# backplane.net
KiCad netlist of a schematic drawn in EAGLE
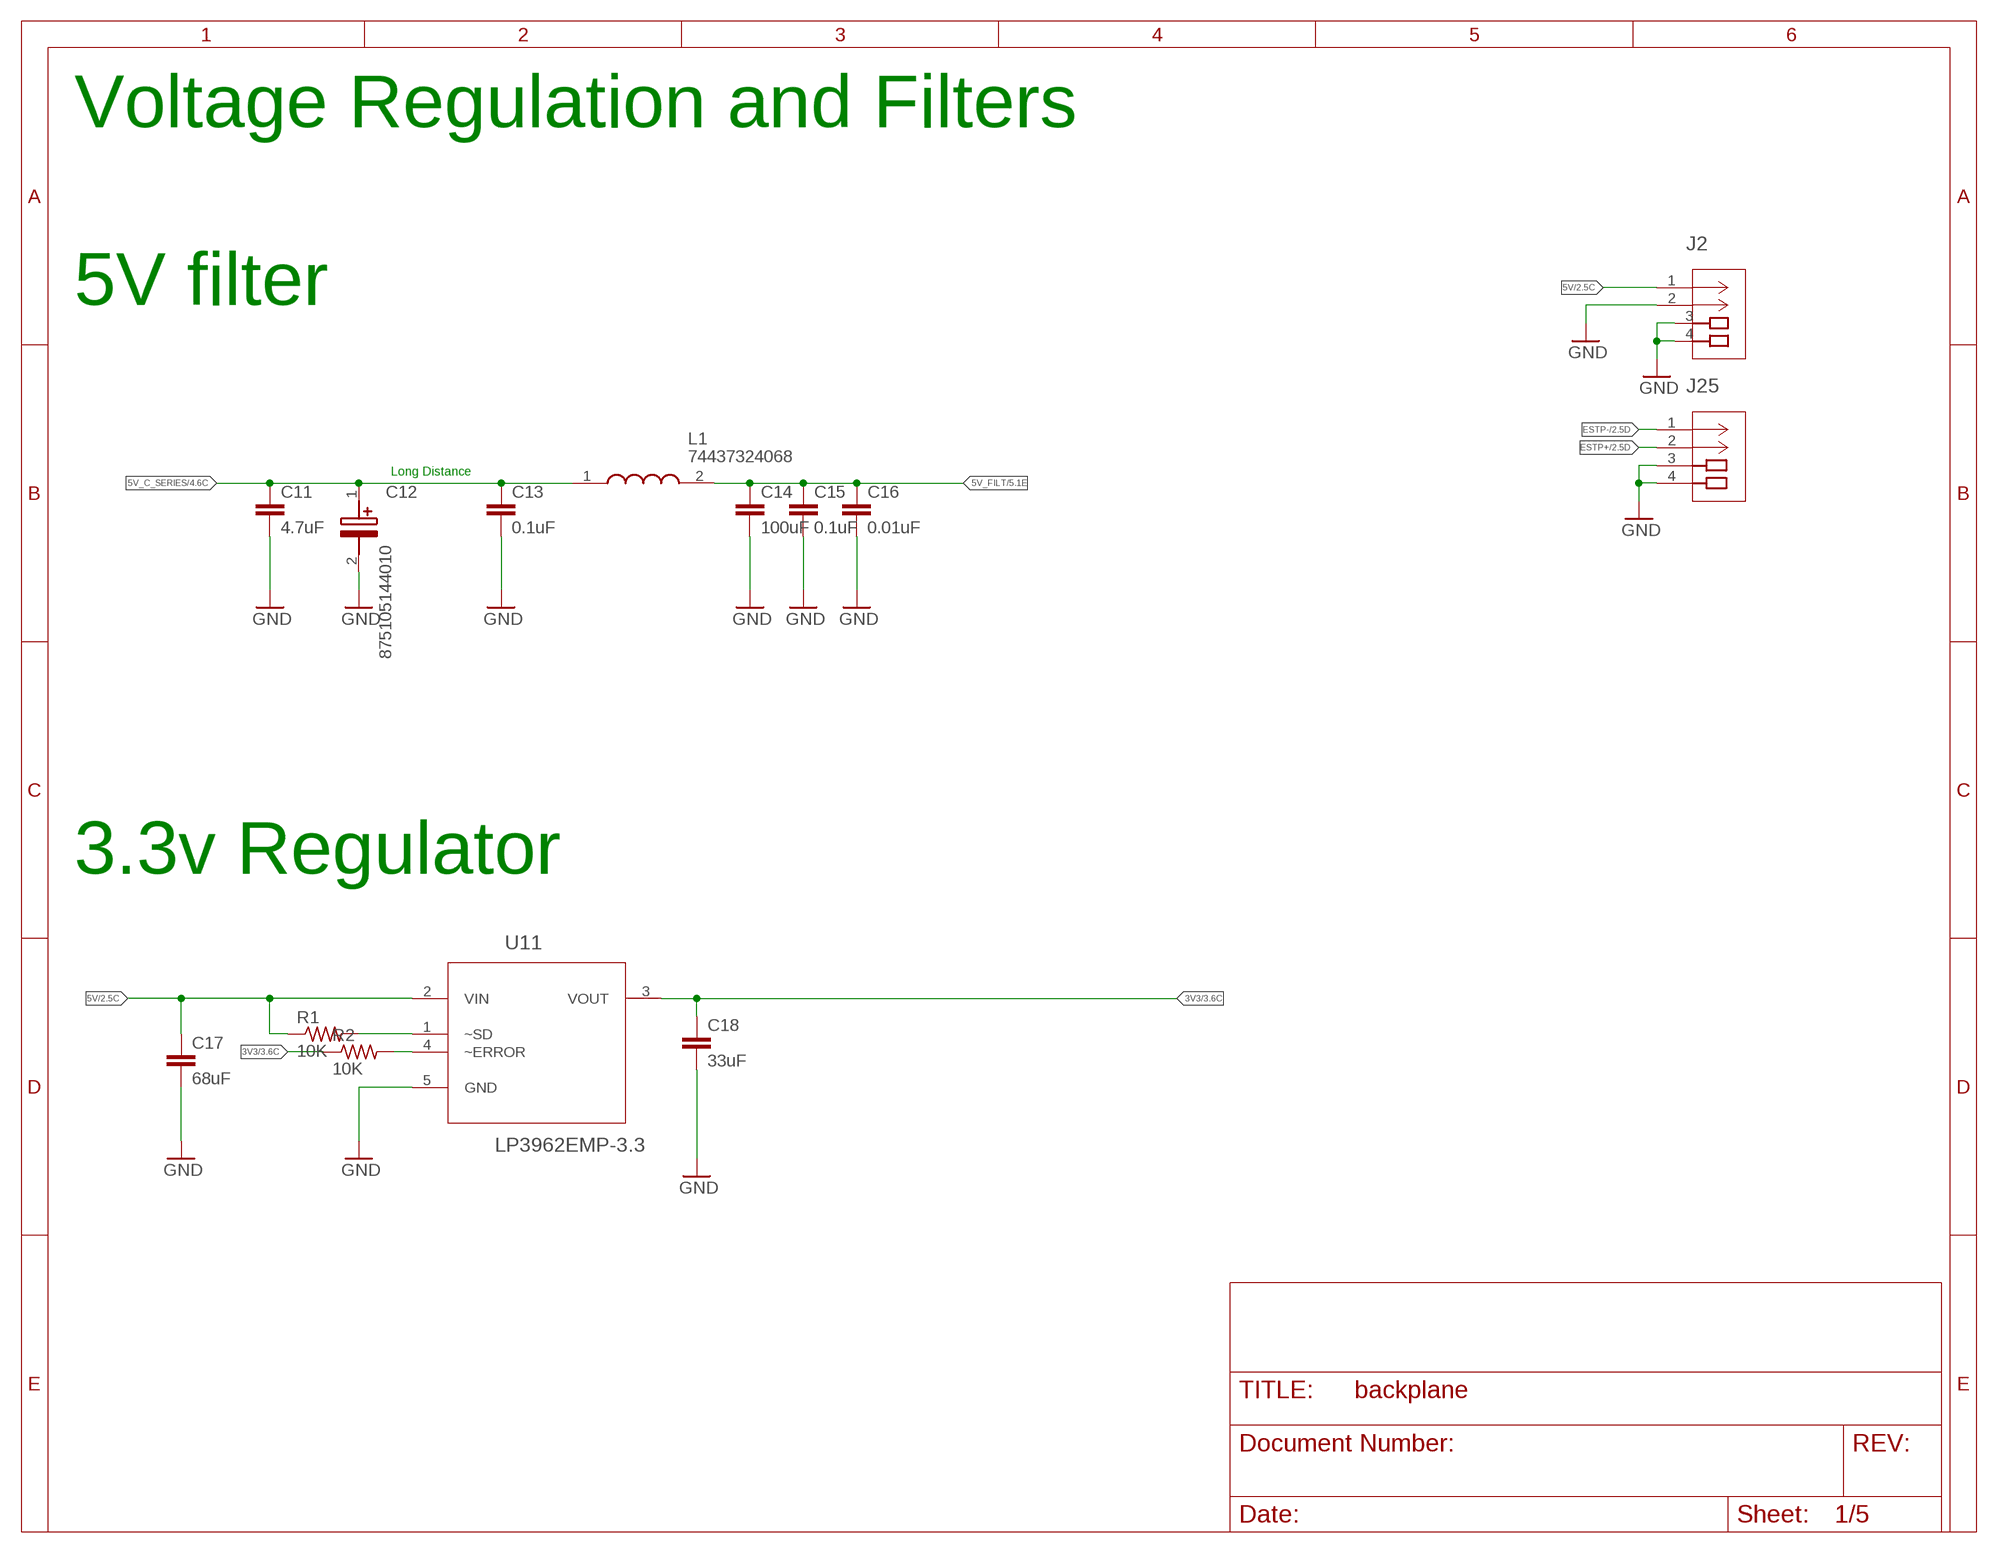
[diagram p0: schematic, sheet 1]
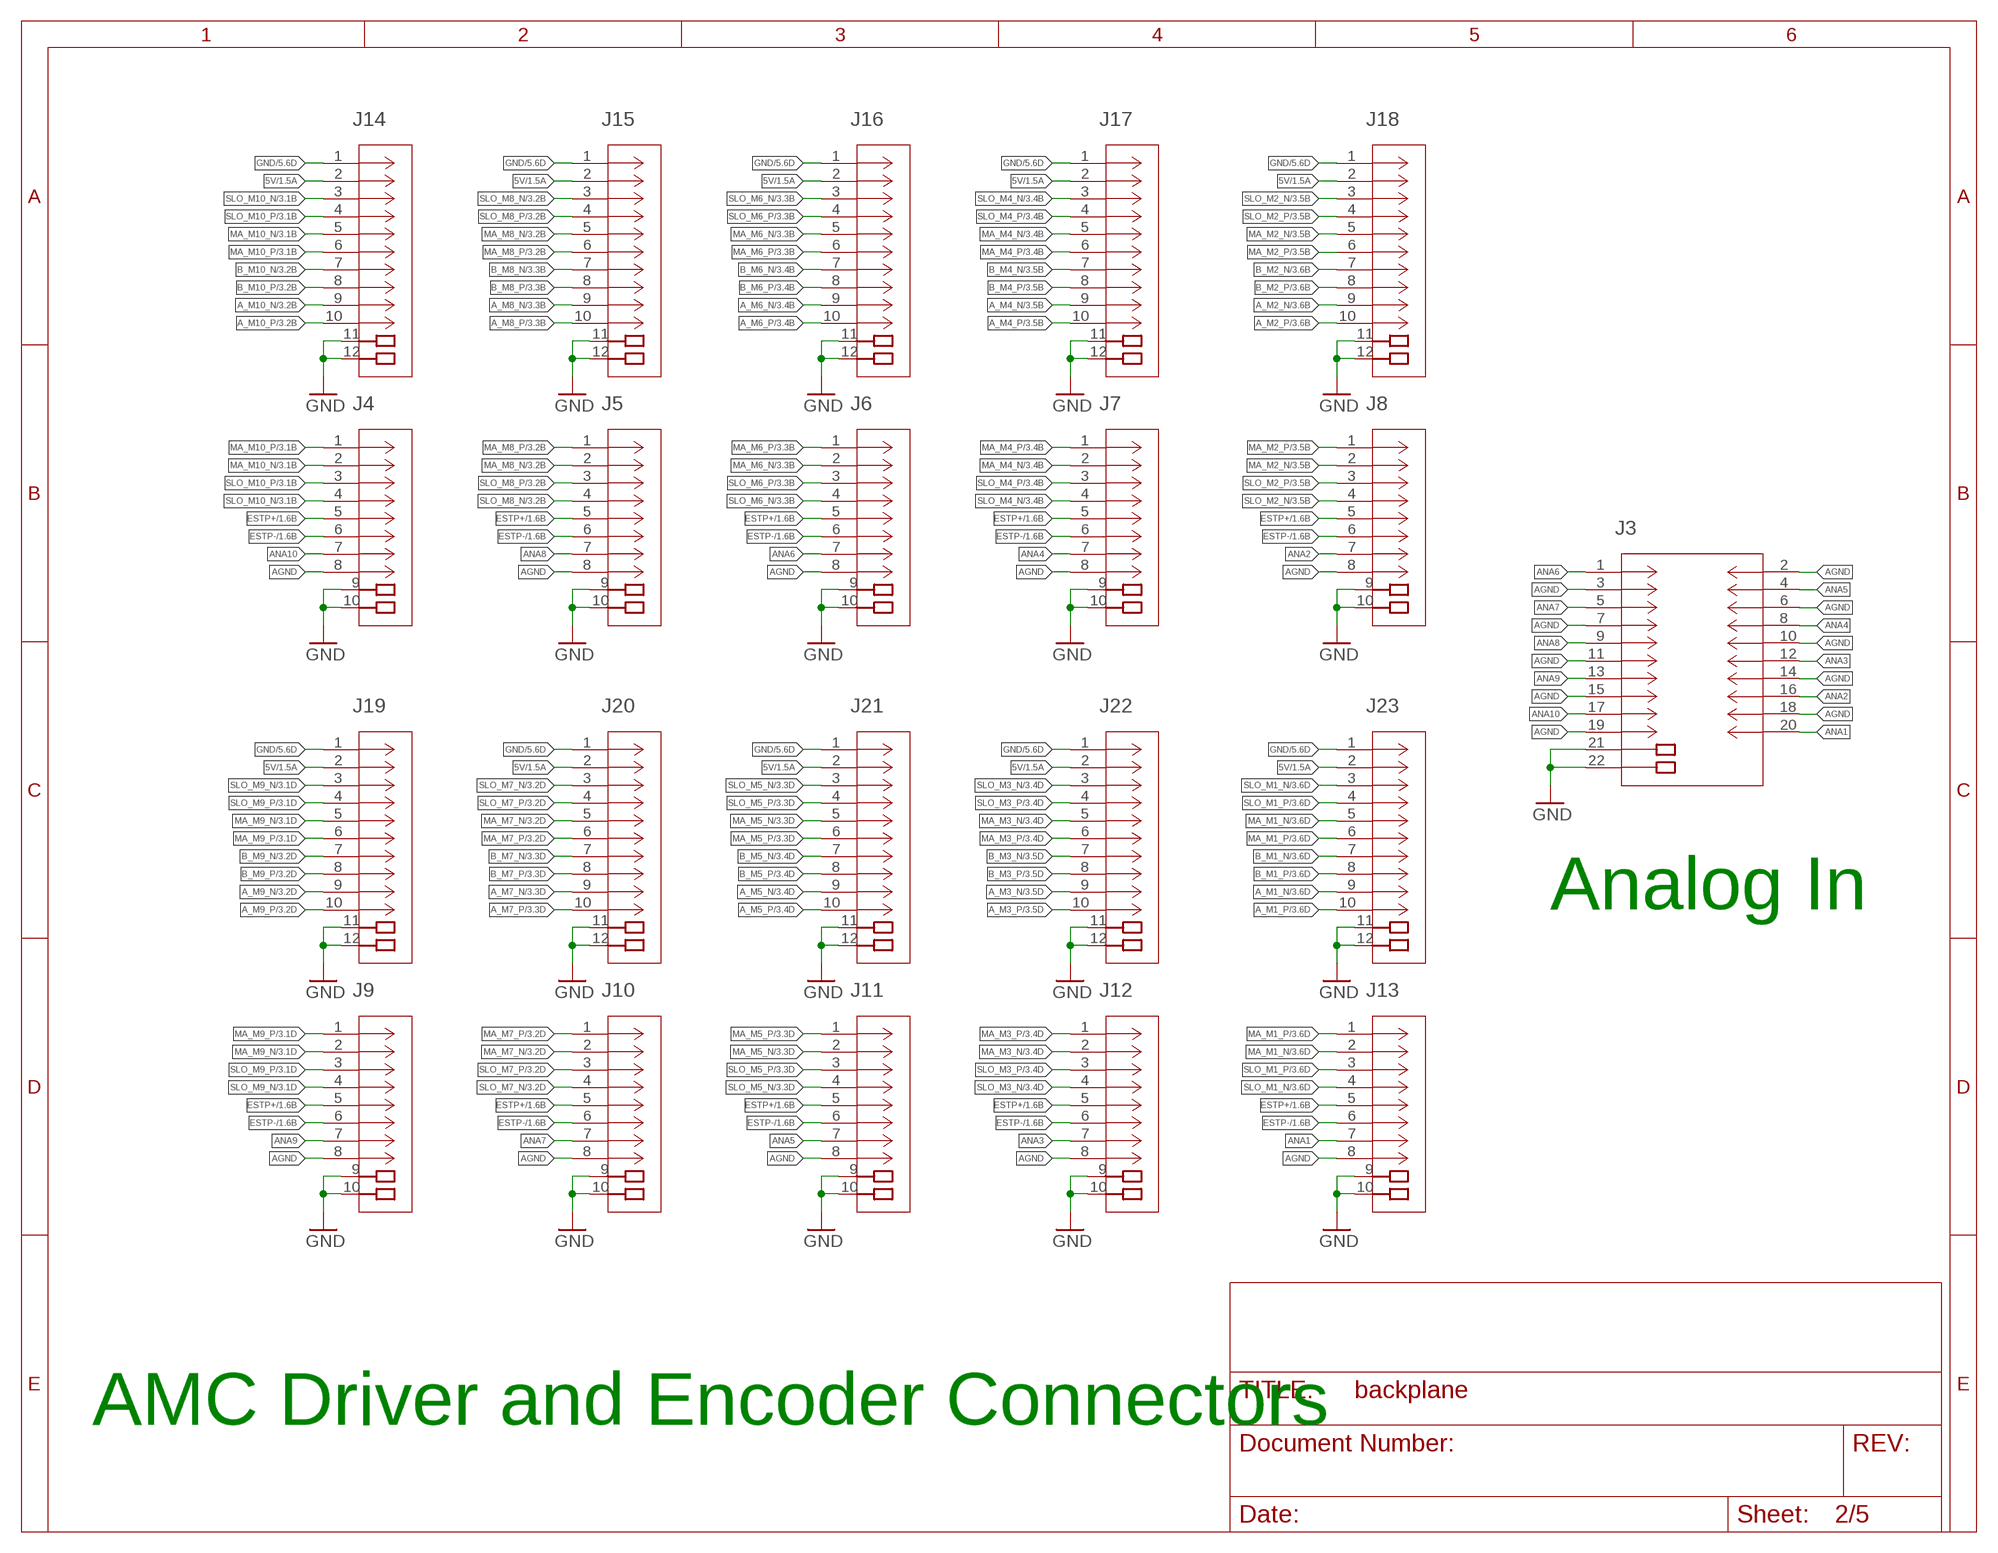
[diagram p1: schematic, sheet 2]
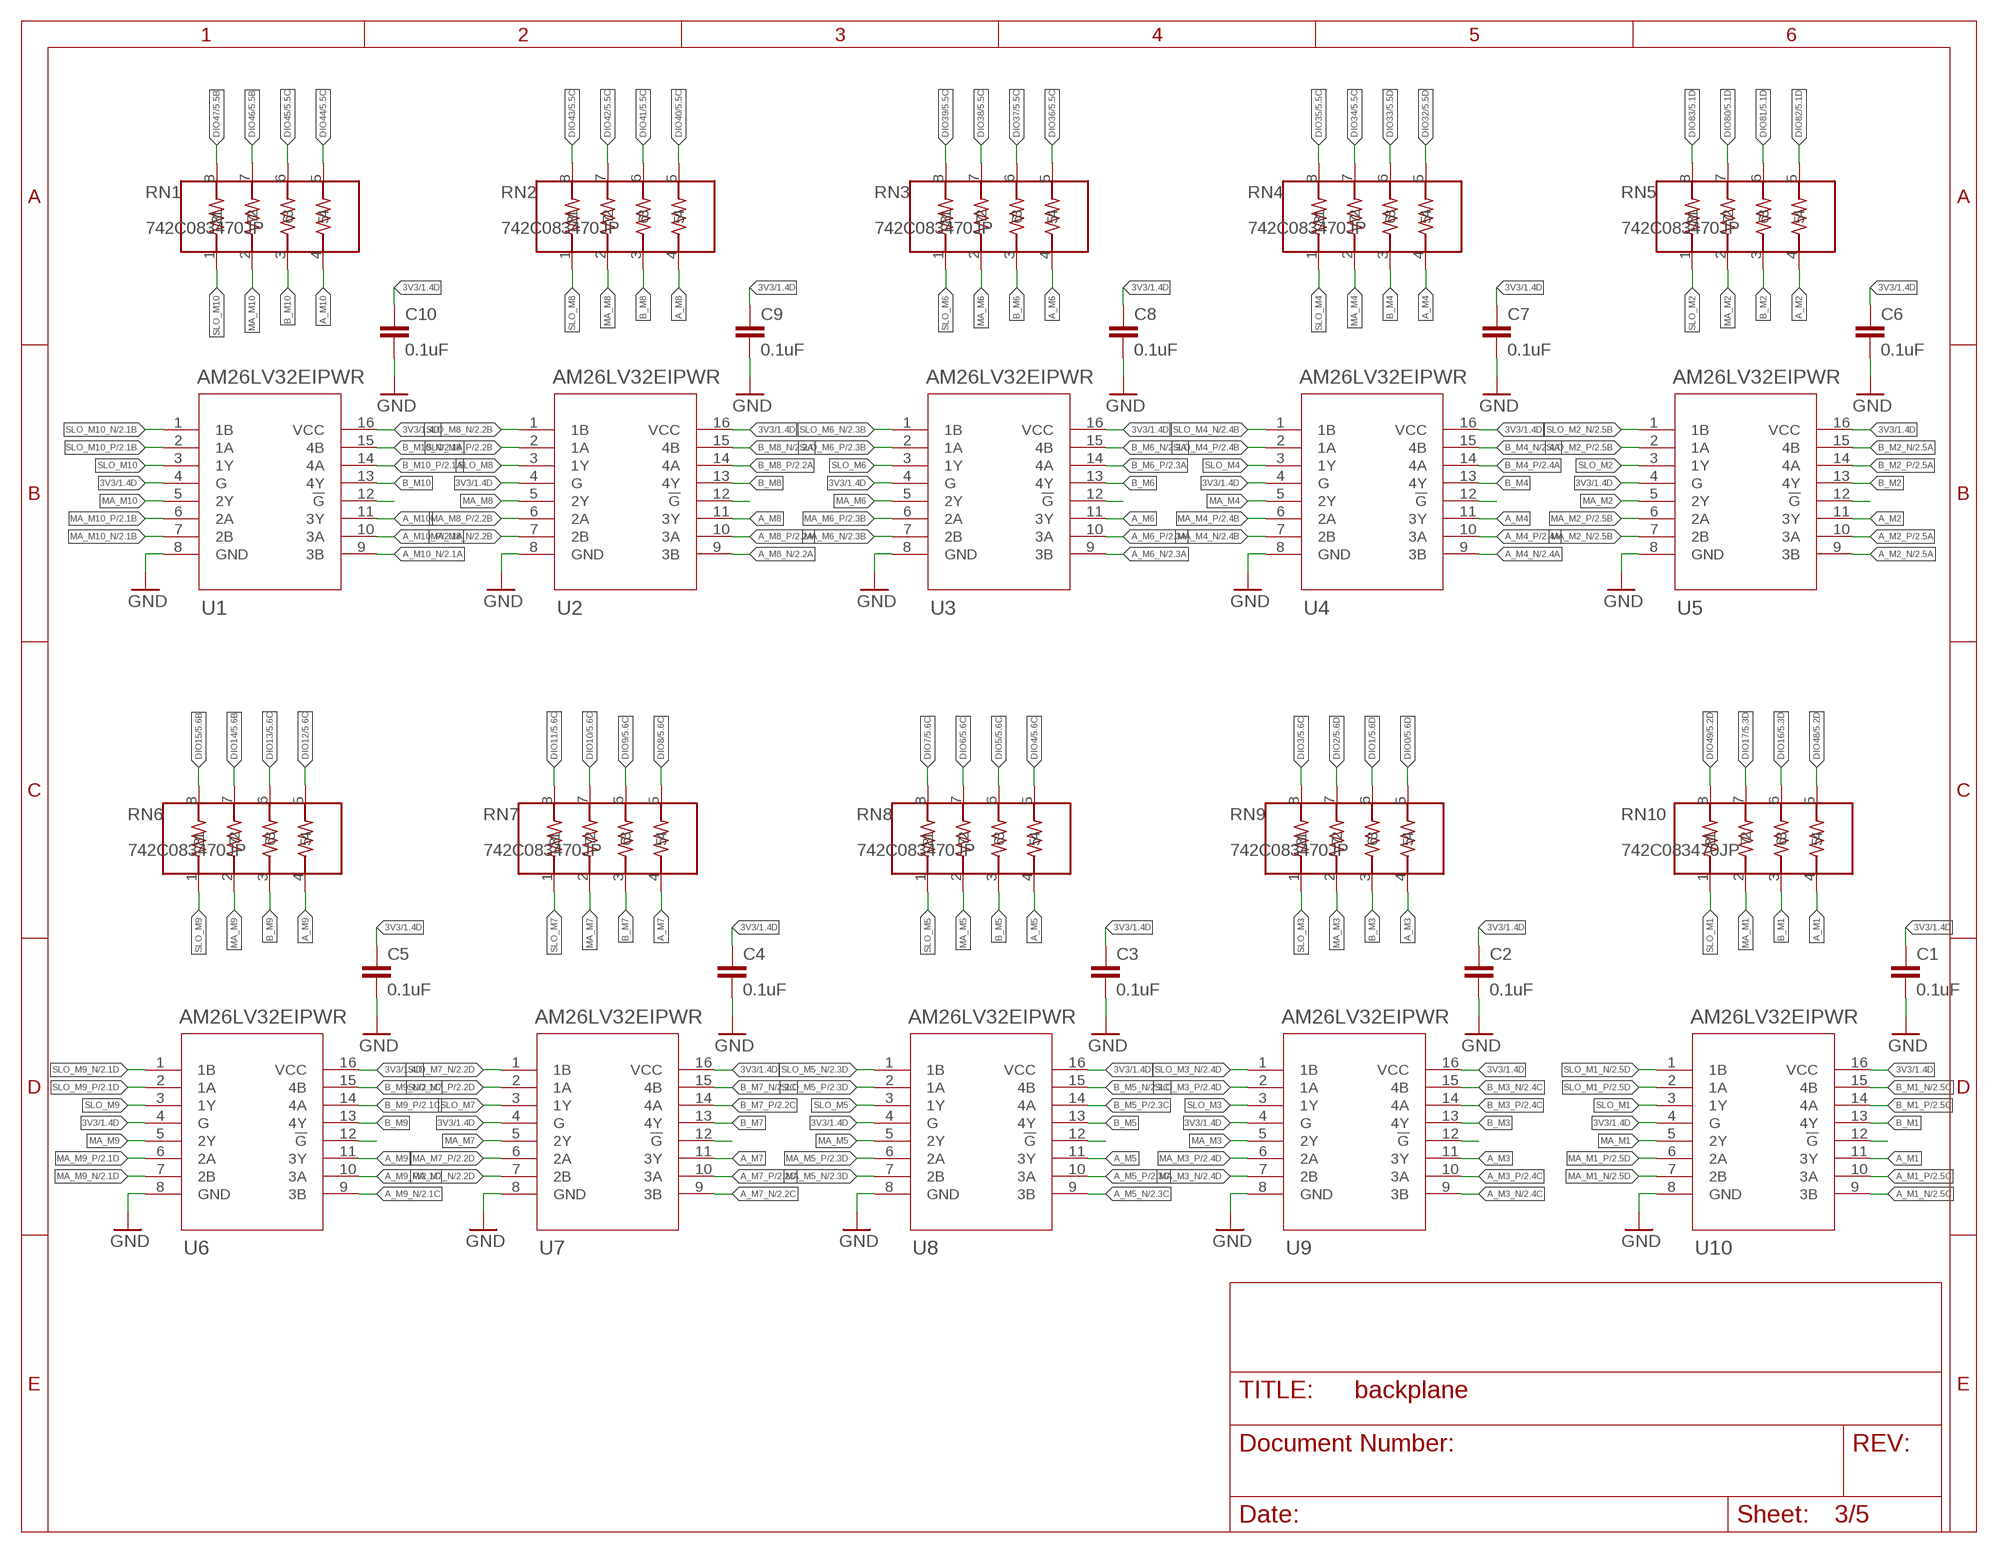
[diagram p2: schematic, sheet 3]
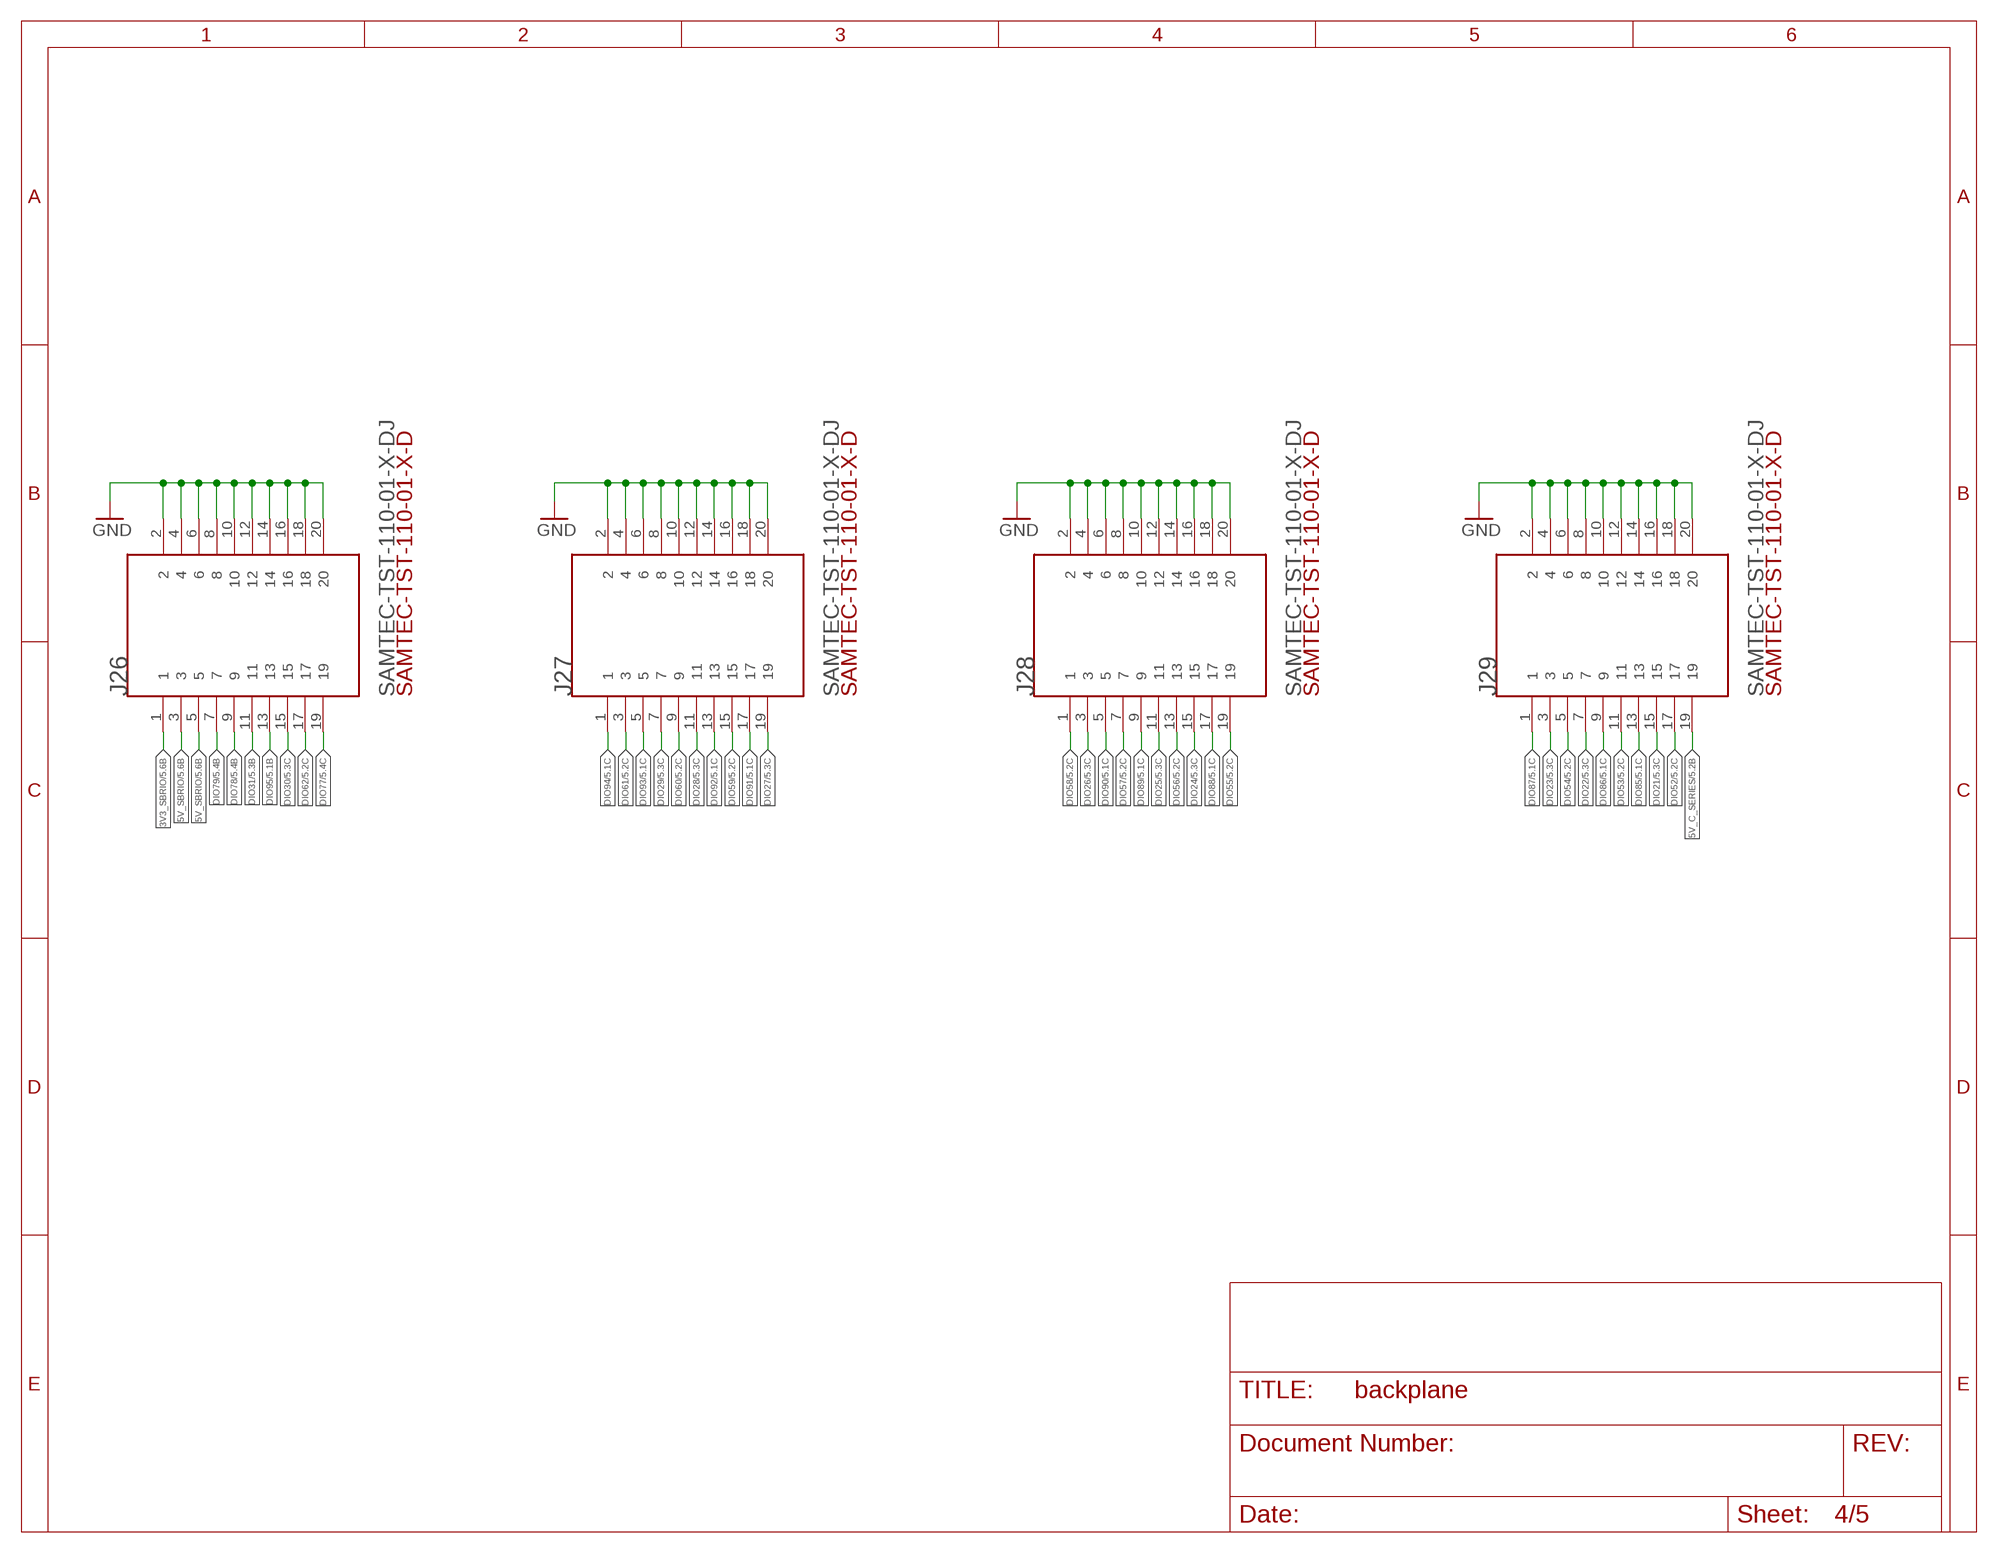
[diagram p3: schematic, sheet 4]
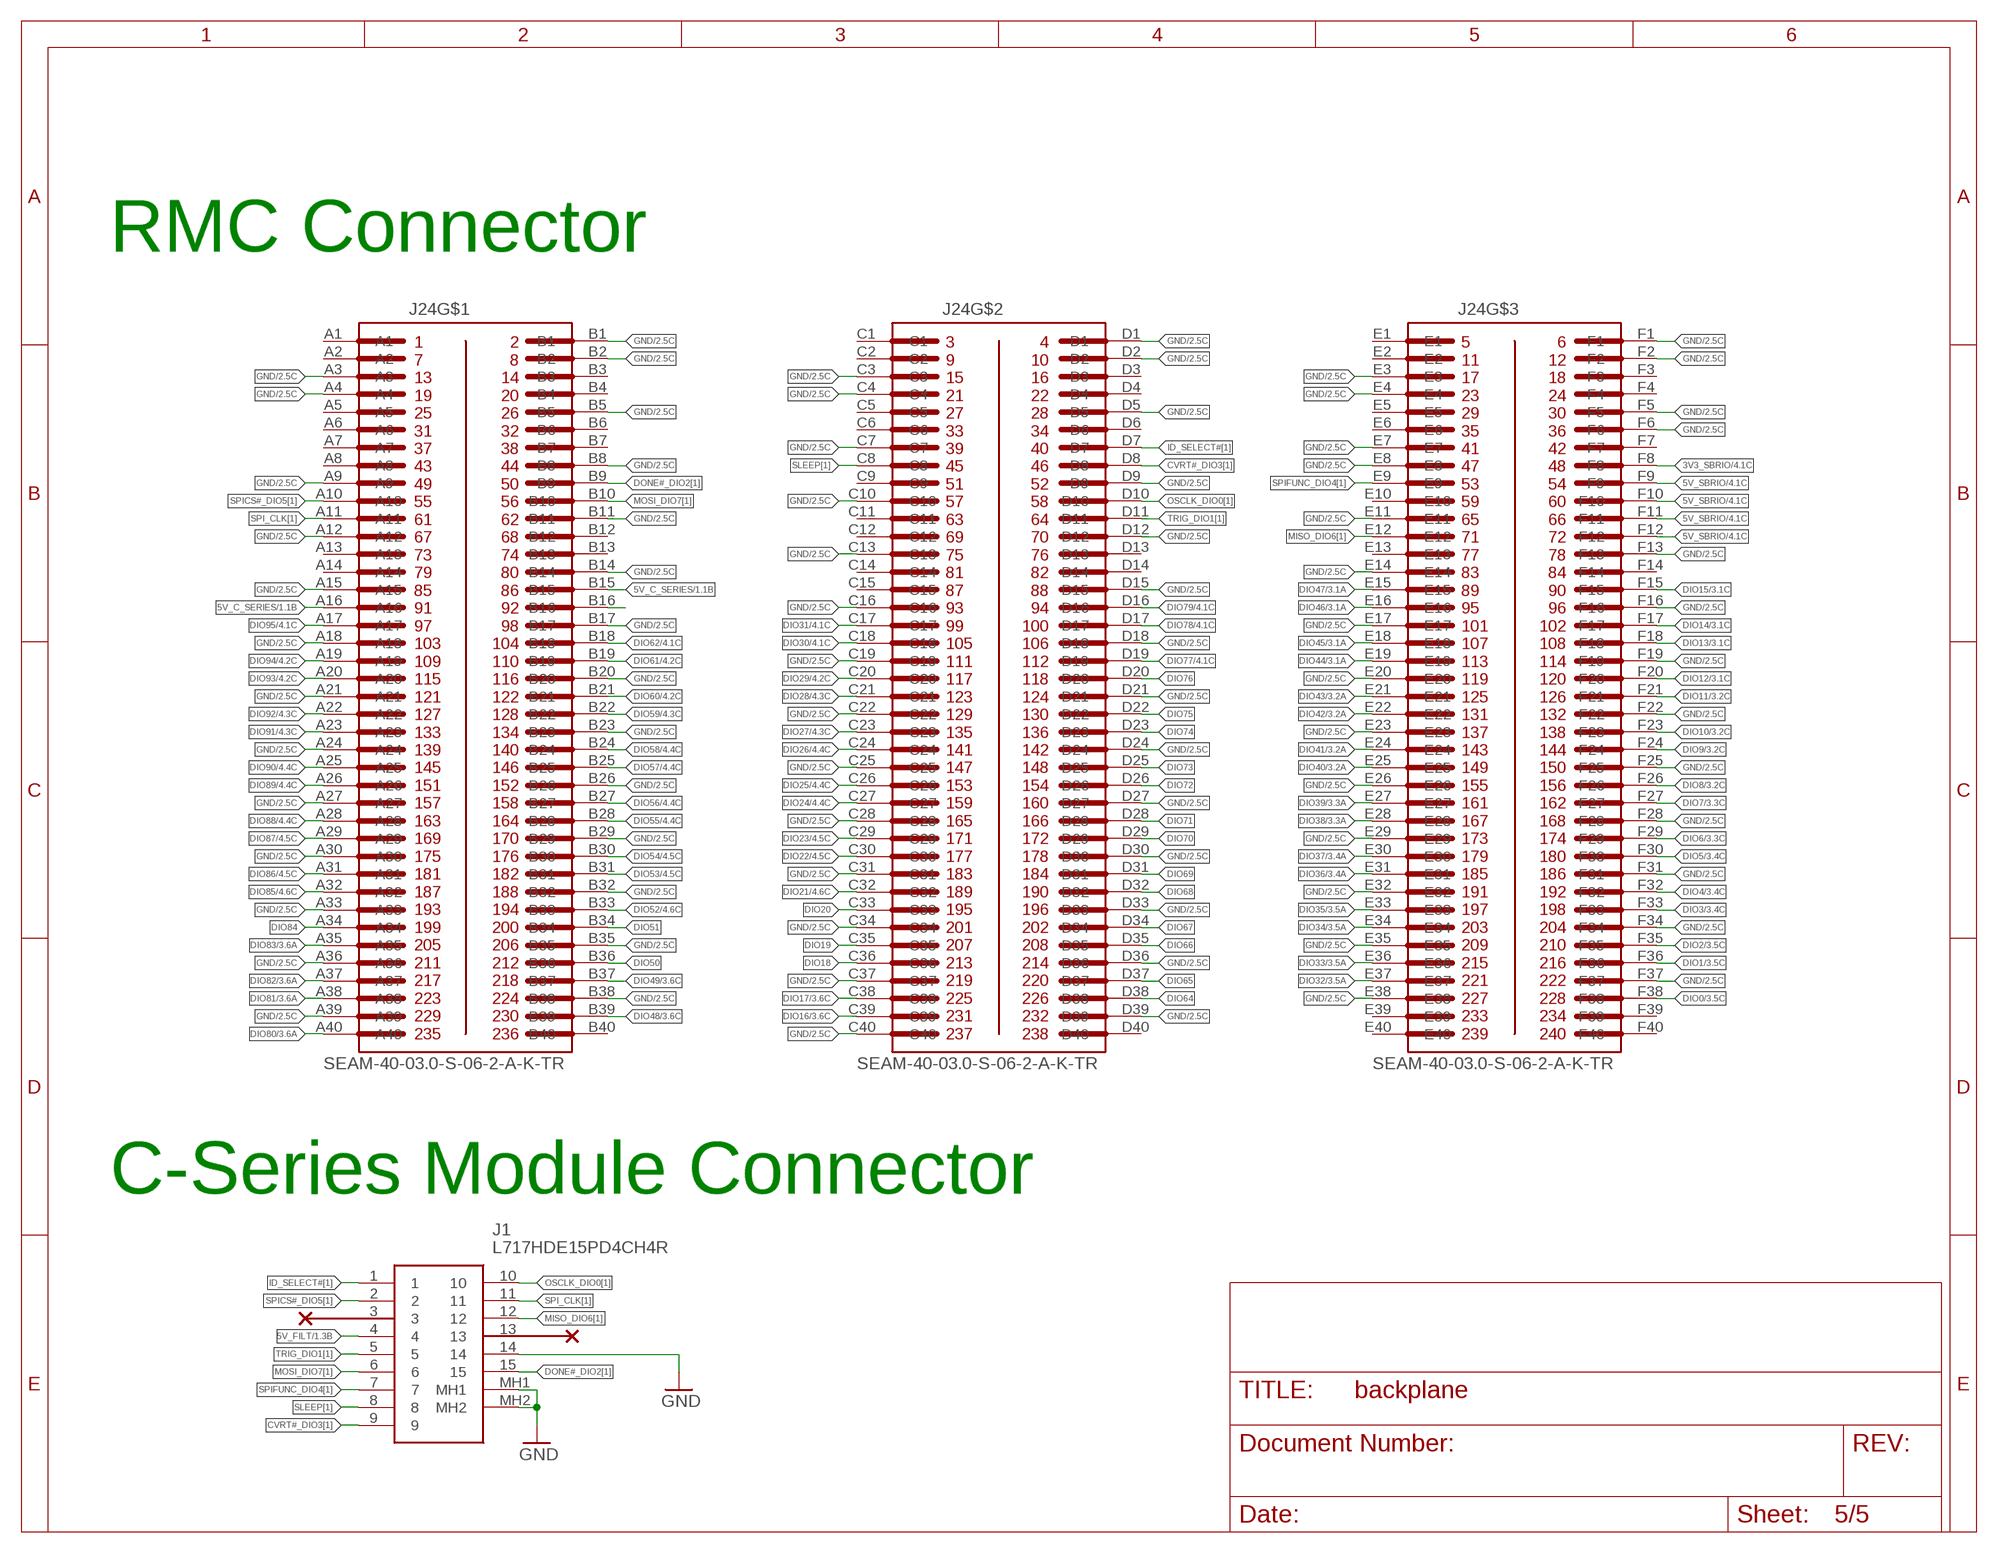
[diagram p4: schematic, sheet 5]

(export (version "E")
  (design (tool "Eeschema 10.0.6"))
  (components
    (comp (ref "J3")
      (value "5011902017")
      (footprint "eagle-import:CON_5011902017")
      (fields (field (name "COPYRIGHT") "Copyright (C) 2022 Ultra Librarian. All rights reserved."))
      (libsource (lib "eagle-import") (part "5011902017"))
    )
    (comp (ref "J4")
      (value "5013310807")
      (footprint "eagle-import:CON_5013310807")
      (fields (field (name "COPYRIGHT") "Copyright (C) 2022 Ultra Librarian. All rights reserved."))
      (libsource (lib "eagle-import") (part "5013310807"))
    )
    (comp (ref "J5")
      (value "5013310807")
      (footprint "eagle-import:CON_5013310807")
      (fields (field (name "COPYRIGHT") "Copyright (C) 2022 Ultra Librarian. All rights reserved."))
      (libsource (lib "eagle-import") (part "5013310807"))
    )
    (comp (ref "J6")
      (value "5013310807")
      (footprint "eagle-import:CON_5013310807")
      (fields (field (name "COPYRIGHT") "Copyright (C) 2022 Ultra Librarian. All rights reserved."))
      (libsource (lib "eagle-import") (part "5013310807"))
    )
    (comp (ref "J7")
      (value "5013310807")
      (footprint "eagle-import:CON_5013310807")
      (fields (field (name "COPYRIGHT") "Copyright (C) 2022 Ultra Librarian. All rights reserved."))
      (libsource (lib "eagle-import") (part "5013310807"))
    )
    (comp (ref "J8")
      (value "5013310807")
      (footprint "eagle-import:CON_5013310807")
      (fields (field (name "COPYRIGHT") "Copyright (C) 2022 Ultra Librarian. All rights reserved."))
      (libsource (lib "eagle-import") (part "5013310807"))
    )
    (comp (ref "J9")
      (value "5013310807")
      (footprint "eagle-import:CON_5013310807")
      (fields (field (name "COPYRIGHT") "Copyright (C) 2022 Ultra Librarian. All rights reserved."))
      (libsource (lib "eagle-import") (part "5013310807"))
    )
    (comp (ref "J10")
      (value "5013310807")
      (footprint "eagle-import:CON_5013310807")
      (fields (field (name "COPYRIGHT") "Copyright (C) 2022 Ultra Librarian. All rights reserved."))
      (libsource (lib "eagle-import") (part "5013310807"))
    )
    (comp (ref "J11")
      (value "5013310807")
      (footprint "eagle-import:CON_5013310807")
      (fields (field (name "COPYRIGHT") "Copyright (C) 2022 Ultra Librarian. All rights reserved."))
      (libsource (lib "eagle-import") (part "5013310807"))
    )
    (comp (ref "J12")
      (value "5013310807")
      (footprint "eagle-import:CON_5013310807")
      (fields (field (name "COPYRIGHT") "Copyright (C) 2022 Ultra Librarian. All rights reserved."))
      (libsource (lib "eagle-import") (part "5013310807"))
    )
    (comp (ref "J13")
      (value "5013310807")
      (footprint "eagle-import:CON_5013310807")
      (fields (field (name "COPYRIGHT") "Copyright (C) 2022 Ultra Librarian. All rights reserved."))
      (libsource (lib "eagle-import") (part "5013310807"))
    )
    (comp (ref "J14")
      (value "5013311007")
      (footprint "eagle-import:CON_5013311007")
      (fields (field (name "COPYRIGHT") "Copyright (C) 2022 Ultra Librarian. All rights reserved."))
      (libsource (lib "eagle-import") (part "5013311007"))
    )
    (comp (ref "J15")
      (value "5013311007")
      (footprint "eagle-import:CON_5013311007")
      (fields (field (name "COPYRIGHT") "Copyright (C) 2022 Ultra Librarian. All rights reserved."))
      (libsource (lib "eagle-import") (part "5013311007"))
    )
    (comp (ref "J16")
      (value "5013311007")
      (footprint "eagle-import:CON_5013311007")
      (fields (field (name "COPYRIGHT") "Copyright (C) 2022 Ultra Librarian. All rights reserved."))
      (libsource (lib "eagle-import") (part "5013311007"))
    )
    (comp (ref "J17")
      (value "5013311007")
      (footprint "eagle-import:CON_5013311007")
      (fields (field (name "COPYRIGHT") "Copyright (C) 2022 Ultra Librarian. All rights reserved."))
      (libsource (lib "eagle-import") (part "5013311007"))
    )
    (comp (ref "J18")
      (value "5013311007")
      (footprint "eagle-import:CON_5013311007")
      (fields (field (name "COPYRIGHT") "Copyright (C) 2022 Ultra Librarian. All rights reserved."))
      (libsource (lib "eagle-import") (part "5013311007"))
    )
    (comp (ref "J19")
      (value "5013311007")
      (footprint "eagle-import:CON_5013311007")
      (fields (field (name "COPYRIGHT") "Copyright (C) 2022 Ultra Librarian. All rights reserved."))
      (libsource (lib "eagle-import") (part "5013311007"))
    )
    (comp (ref "J20")
      (value "5013311007")
      (footprint "eagle-import:CON_5013311007")
      (fields (field (name "COPYRIGHT") "Copyright (C) 2022 Ultra Librarian. All rights reserved."))
      (libsource (lib "eagle-import") (part "5013311007"))
    )
    (comp (ref "J21")
      (value "5013311007")
      (footprint "eagle-import:CON_5013311007")
      (fields (field (name "COPYRIGHT") "Copyright (C) 2022 Ultra Librarian. All rights reserved."))
      (libsource (lib "eagle-import") (part "5013311007"))
    )
    (comp (ref "J22")
      (value "5013311007")
      (footprint "eagle-import:CON_5013311007")
      (fields (field (name "COPYRIGHT") "Copyright (C) 2022 Ultra Librarian. All rights reserved."))
      (libsource (lib "eagle-import") (part "5013311007"))
    )
    (comp (ref "J23")
      (value "5013311007")
      (footprint "eagle-import:CON_5013311007")
      (fields (field (name "COPYRIGHT") "Copyright (C) 2022 Ultra Librarian. All rights reserved."))
      (libsource (lib "eagle-import") (part "5013311007"))
    )
    (comp (ref "C11")
      (value "4.7uF")
      (footprint "eagle-import:C0603")
      (libsource (lib "eagle-import") (part "C-EUC0603"))
    )
    (comp (ref "C12")
      (value "875105144010")
      (footprint "eagle-import:CAPAE660X580N")
      (fields (field (name "MOUSER_PART_NUMBER") "710-875105144010"))
      (libsource (lib "eagle-import") (part "875105144010"))
    )
    (comp (ref "C13")
      (value "0.1uF")
      (footprint "eagle-import:C0603")
      (libsource (lib "eagle-import") (part "C-EUC0603"))
    )
    (comp (ref "C14")
      (value "100uF")
      (footprint "eagle-import:C1206")
      (libsource (lib "eagle-import") (part "C-EUC1206"))
    )
    (comp (ref "C15")
      (value "0.1uF")
      (footprint "eagle-import:C0603")
      (libsource (lib "eagle-import") (part "C-EUC0603"))
    )
    (comp (ref "C16")
      (value "0.01uF")
      (footprint "eagle-import:C0603")
      (libsource (lib "eagle-import") (part "C-EUC0603"))
    )
    (comp (ref "C17")
      (value "68uF")
      (footprint "eagle-import:C1206")
      (libsource (lib "eagle-import") (part "C-EUC1206"))
    )
    (comp (ref "C18")
      (value "33uF")
      (footprint "eagle-import:C1206")
      (libsource (lib "eagle-import") (part "C-EUC1206"))
    )
    (comp (ref "J2")
      (value "1054301102")
      (footprint "eagle-import:CON_1054301102_MOL")
      (fields (field (name "COPYRIGHT") "Copyright (C) 2022 Ultra Librarian. All rights reserved."))
      (libsource (lib "eagle-import") (part "1054301102"))
    )
    (comp (ref "J25")
      (value "5055670271")
      (footprint "eagle-import:CON_5055670271")
      (fields (field (name "COPYRIGHT") "Copyright (C) 2022 Ultra Librarian. All rights reserved."))
      (libsource (lib "eagle-import") (part "5055670271"))
    )
    (comp (ref "L1")
      (value "74437324068")
      (footprint "eagle-import:WE-LHMI_402048")
      (fields (field (name "MOUSER_PART_NUMBER") "710-74437324068"))
      (libsource (lib "eagle-import") (part "74437324068"))
    )
    (comp (ref "R1")
      (value "10K")
      (footprint "eagle-import:R0603")
      (libsource (lib "eagle-import") (part "R-US_R0603"))
    )
    (comp (ref "R2")
      (value "10K")
      (footprint "eagle-import:R0603")
      (libsource (lib "eagle-import") (part "R-US_R0603"))
    )
    (comp (ref "U11")
      (value "LP3962EMP-3.3")
      (footprint "eagle-import:SOT150P696X180-5N")
      (fields
        (field (name "DIGI-KEY_PART_NUMBER") "LP3962EMP-3.3/NOPBTR-ND")
        (field (name "MF") "Texas Instruments")
        (field (name "MP") "LP3962EMP-3.3/NOPB")
      )
      (libsource (lib "eagle-import") (part "LP3962EMP-3.3"))
    )
    (comp (ref "J26")
      (value "SAMTEC-TST-110-01-X-DJ")
      (footprint "eagle-import:SAMTEC-TST-110-01-X-D")
      (fields
        (field (name "DIGI-KEY_PART_NUMBER") "SAM13027-ND")
        (field (name "MF") "Samtec")
        (field (name "MP") "TST-110-01-S-D")
      )
      (libsource (lib "eagle-import") (part "SAMTEC-TST-110-01-X-DJ"))
    )
    (comp (ref "J27")
      (value "SAMTEC-TST-110-01-X-DJ")
      (footprint "eagle-import:SAMTEC-TST-110-01-X-D")
      (fields
        (field (name "DIGI-KEY_PART_NUMBER") "SAM13027-ND")
        (field (name "MF") "Samtec")
        (field (name "MP") "TST-110-01-S-D")
      )
      (libsource (lib "eagle-import") (part "SAMTEC-TST-110-01-X-DJ"))
    )
    (comp (ref "J28")
      (value "SAMTEC-TST-110-01-X-DJ")
      (footprint "eagle-import:SAMTEC-TST-110-01-X-D")
      (fields
        (field (name "DIGI-KEY_PART_NUMBER") "SAM13027-ND")
        (field (name "MF") "Samtec")
        (field (name "MP") "TST-110-01-S-D")
      )
      (libsource (lib "eagle-import") (part "SAMTEC-TST-110-01-X-DJ"))
    )
    (comp (ref "J29")
      (value "SAMTEC-TST-110-01-X-DJ")
      (footprint "eagle-import:SAMTEC-TST-110-01-X-D")
      (fields
        (field (name "DIGI-KEY_PART_NUMBER") "SAM13027-ND")
        (field (name "MF") "Samtec")
        (field (name "MP") "TST-110-01-S-D")
      )
      (libsource (lib "eagle-import") (part "SAMTEC-TST-110-01-X-DJ"))
    )
    (comp (ref "J1")
      (value "L717HDE15PD4CH4R")
      (footprint "eagle-import:L717HDE15PD4CH4R")
      (fields (field (name "MOUSER_PART_NUMBER") "523-L717HDE15PD4CH4R"))
      (libsource (lib "eagle-import") (part "L717HDE15PD4CH4R"))
    )
    (comp (ref "J24")
      (value "SEAM-40-03.0-S-06-2-A-K-TR")
      (footprint "eagle-import:SAMTEC_SEAM-40-03.0-S-06-2-A-K-TR")
      (fields (field (name "MF") "Samtec"))
      (libsource (lib "eagle-import") (part "SEAM-40-03.0-S-06-2-A-K-TR"))
    )
    (comp (ref "C1")
      (value "0.1uF")
      (footprint "eagle-import:C0603")
      (libsource (lib "eagle-import") (part "C-EUC0603"))
    )
    (comp (ref "C2")
      (value "0.1uF")
      (footprint "eagle-import:C0603")
      (libsource (lib "eagle-import") (part "C-EUC0603"))
    )
    (comp (ref "C3")
      (value "0.1uF")
      (footprint "eagle-import:C0603")
      (libsource (lib "eagle-import") (part "C-EUC0603"))
    )
    (comp (ref "C4")
      (value "0.1uF")
      (footprint "eagle-import:C0603")
      (libsource (lib "eagle-import") (part "C-EUC0603"))
    )
    (comp (ref "C5")
      (value "0.1uF")
      (footprint "eagle-import:C0603")
      (libsource (lib "eagle-import") (part "C-EUC0603"))
    )
    (comp (ref "C6")
      (value "0.1uF")
      (footprint "eagle-import:C0603")
      (libsource (lib "eagle-import") (part "C-EUC0603"))
    )
    (comp (ref "C7")
      (value "0.1uF")
      (footprint "eagle-import:C0603")
      (libsource (lib "eagle-import") (part "C-EUC0603"))
    )
    (comp (ref "C8")
      (value "0.1uF")
      (footprint "eagle-import:C0603")
      (libsource (lib "eagle-import") (part "C-EUC0603"))
    )
    (comp (ref "C9")
      (value "0.1uF")
      (footprint "eagle-import:C0603")
      (libsource (lib "eagle-import") (part "C-EUC0603"))
    )
    (comp (ref "C10")
      (value "0.1uF")
      (footprint "eagle-import:C0603")
      (libsource (lib "eagle-import") (part "C-EUC0603"))
    )
    (comp (ref "RN1")
      (value "742C083470JP")
      (footprint "eagle-import:RESCAV80P320X160X70-8N")
      (fields (field (name "DIGI-KEY_PART_NUMBER") "742C083470JPTR-ND") (field (name "MF") "CTS Components"))
      (libsource (lib "eagle-import") (part "742C083470JP"))
    )
    (comp (ref "RN2")
      (value "742C083470JP")
      (footprint "eagle-import:RESCAV80P320X160X70-8N")
      (fields (field (name "DIGI-KEY_PART_NUMBER") "742C083470JPTR-ND") (field (name "MF") "CTS Components"))
      (libsource (lib "eagle-import") (part "742C083470JP"))
    )
    (comp (ref "RN3")
      (value "742C083470JP")
      (footprint "eagle-import:RESCAV80P320X160X70-8N")
      (fields (field (name "DIGI-KEY_PART_NUMBER") "742C083470JPTR-ND") (field (name "MF") "CTS Components"))
      (libsource (lib "eagle-import") (part "742C083470JP"))
    )
    (comp (ref "RN4")
      (value "742C083470JP")
      (footprint "eagle-import:RESCAV80P320X160X70-8N")
      (fields (field (name "DIGI-KEY_PART_NUMBER") "742C083470JPTR-ND") (field (name "MF") "CTS Components"))
      (libsource (lib "eagle-import") (part "742C083470JP"))
    )
    (comp (ref "RN5")
      (value "742C083470JP")
      (footprint "eagle-import:RESCAV80P320X160X70-8N")
      (fields (field (name "DIGI-KEY_PART_NUMBER") "742C083470JPTR-ND") (field (name "MF") "CTS Components"))
      (libsource (lib "eagle-import") (part "742C083470JP"))
    )
    (comp (ref "RN6")
      (value "742C083470JP")
      (footprint "eagle-import:RESCAV80P320X160X70-8N")
      (fields (field (name "DIGI-KEY_PART_NUMBER") "742C083470JPTR-ND") (field (name "MF") "CTS Components"))
      (libsource (lib "eagle-import") (part "742C083470JP"))
    )
    (comp (ref "RN7")
      (value "742C083470JP")
      (footprint "eagle-import:RESCAV80P320X160X70-8N")
      (fields (field (name "DIGI-KEY_PART_NUMBER") "742C083470JPTR-ND") (field (name "MF") "CTS Components"))
      (libsource (lib "eagle-import") (part "742C083470JP"))
    )
    (comp (ref "RN8")
      (value "742C083470JP")
      (footprint "eagle-import:RESCAV80P320X160X70-8N")
      (fields (field (name "DIGI-KEY_PART_NUMBER") "742C083470JPTR-ND") (field (name "MF") "CTS Components"))
      (libsource (lib "eagle-import") (part "742C083470JP"))
    )
    (comp (ref "RN9")
      (value "742C083470JP")
      (footprint "eagle-import:RESCAV80P320X160X70-8N")
      (fields (field (name "DIGI-KEY_PART_NUMBER") "742C083470JPTR-ND") (field (name "MF") "CTS Components"))
      (libsource (lib "eagle-import") (part "742C083470JP"))
    )
    (comp (ref "RN10")
      (value "742C083470JP")
      (footprint "eagle-import:RESCAV80P320X160X70-8N")
      (fields (field (name "DIGI-KEY_PART_NUMBER") "742C083470JPTR-ND") (field (name "MF") "CTS Components"))
      (libsource (lib "eagle-import") (part "742C083470JP"))
    )
    (comp (ref "U1")
      (value "AM26LV32EIPWR")
      (footprint "eagle-import:PW16")
      (fields (field (name "COPYRIGHT") "Copyright (C) 2022 Ultra Librarian. All rights reserved."))
      (libsource (lib "eagle-import") (part "AM26LV32EIPWR"))
    )
    (comp (ref "U2")
      (value "AM26LV32EIPWR")
      (footprint "eagle-import:PW16")
      (fields (field (name "COPYRIGHT") "Copyright (C) 2022 Ultra Librarian. All rights reserved."))
      (libsource (lib "eagle-import") (part "AM26LV32EIPWR"))
    )
    (comp (ref "U3")
      (value "AM26LV32EIPWR")
      (footprint "eagle-import:PW16")
      (fields (field (name "COPYRIGHT") "Copyright (C) 2022 Ultra Librarian. All rights reserved."))
      (libsource (lib "eagle-import") (part "AM26LV32EIPWR"))
    )
    (comp (ref "U4")
      (value "AM26LV32EIPWR")
      (footprint "eagle-import:PW16")
      (fields (field (name "COPYRIGHT") "Copyright (C) 2022 Ultra Librarian. All rights reserved."))
      (libsource (lib "eagle-import") (part "AM26LV32EIPWR"))
    )
    (comp (ref "U5")
      (value "AM26LV32EIPWR")
      (footprint "eagle-import:PW16")
      (fields (field (name "COPYRIGHT") "Copyright (C) 2022 Ultra Librarian. All rights reserved."))
      (libsource (lib "eagle-import") (part "AM26LV32EIPWR"))
    )
    (comp (ref "U6")
      (value "AM26LV32EIPWR")
      (footprint "eagle-import:PW16")
      (fields (field (name "COPYRIGHT") "Copyright (C) 2022 Ultra Librarian. All rights reserved."))
      (libsource (lib "eagle-import") (part "AM26LV32EIPWR"))
    )
    (comp (ref "U7")
      (value "AM26LV32EIPWR")
      (footprint "eagle-import:PW16")
      (fields (field (name "COPYRIGHT") "Copyright (C) 2022 Ultra Librarian. All rights reserved."))
      (libsource (lib "eagle-import") (part "AM26LV32EIPWR"))
    )
    (comp (ref "U8")
      (value "AM26LV32EIPWR")
      (footprint "eagle-import:PW16")
      (fields (field (name "COPYRIGHT") "Copyright (C) 2022 Ultra Librarian. All rights reserved."))
      (libsource (lib "eagle-import") (part "AM26LV32EIPWR"))
    )
    (comp (ref "U9")
      (value "AM26LV32EIPWR")
      (footprint "eagle-import:PW16")
      (fields (field (name "COPYRIGHT") "Copyright (C) 2022 Ultra Librarian. All rights reserved."))
      (libsource (lib "eagle-import") (part "AM26LV32EIPWR"))
    )
    (comp (ref "U10")
      (value "AM26LV32EIPWR")
      (footprint "eagle-import:PW16")
      (fields (field (name "COPYRIGHT") "Copyright (C) 2022 Ultra Librarian. All rights reserved."))
      (libsource (lib "eagle-import") (part "AM26LV32EIPWR"))
    )
  )
  (nets
    (net (code "1") (name "3V3") (class "Default")
      (node (ref "C1") (pin "1") (pinfunction "1_1") (pintype "passive"))
      (node (ref "C10") (pin "1") (pinfunction "1_1") (pintype "passive"))
      (node (ref "C18") (pin "1") (pinfunction "1_1") (pintype "passive"))
      (node (ref "C2") (pin "1") (pinfunction "1_1") (pintype "passive"))
      (node (ref "C3") (pin "1") (pinfunction "1_1") (pintype "passive"))
      (node (ref "C4") (pin "1") (pinfunction "1_1") (pintype "passive"))
      (node (ref "C5") (pin "1") (pinfunction "1_1") (pintype "passive"))
      (node (ref "C6") (pin "1") (pinfunction "1_1") (pintype "passive"))
      (node (ref "C7") (pin "1") (pinfunction "1_1") (pintype "passive"))
      (node (ref "C8") (pin "1") (pinfunction "1_1") (pintype "passive"))
      (node (ref "C9") (pin "1") (pinfunction "1_1") (pintype "passive"))
      (node (ref "R2") (pin "1") (pinfunction "1_1") (pintype "passive"))
      (node (ref "U1") (pin "16") (pinfunction "VCC_16") (pintype "power_in"))
      (node (ref "U1") (pin "4") (pinfunction "G_4") (pintype "passive"))
      (node (ref "U10") (pin "16") (pinfunction "VCC_16") (pintype "power_in"))
      (node (ref "U10") (pin "4") (pinfunction "G_4") (pintype "passive"))
      (node (ref "U11") (pin "3") (pinfunction "VOUT_3") (pintype "output"))
      (node (ref "U2") (pin "16") (pinfunction "VCC_16") (pintype "power_in"))
      (node (ref "U2") (pin "4") (pinfunction "G_4") (pintype "passive"))
      (node (ref "U3") (pin "16") (pinfunction "VCC_16") (pintype "power_in"))
      (node (ref "U3") (pin "4") (pinfunction "G_4") (pintype "passive"))
      (node (ref "U4") (pin "16") (pinfunction "VCC_16") (pintype "power_in"))
      (node (ref "U4") (pin "4") (pinfunction "G_4") (pintype "passive"))
      (node (ref "U5") (pin "16") (pinfunction "VCC_16") (pintype "power_in"))
      (node (ref "U5") (pin "4") (pinfunction "G_4") (pintype "passive"))
      (node (ref "U6") (pin "16") (pinfunction "VCC_16") (pintype "power_in"))
      (node (ref "U6") (pin "4") (pinfunction "G_4") (pintype "passive"))
      (node (ref "U7") (pin "16") (pinfunction "VCC_16") (pintype "power_in"))
      (node (ref "U7") (pin "4") (pinfunction "G_4") (pintype "passive"))
      (node (ref "U8") (pin "16") (pinfunction "VCC_16") (pintype "power_in"))
      (node (ref "U8") (pin "4") (pinfunction "G_4") (pintype "passive"))
      (node (ref "U9") (pin "16") (pinfunction "VCC_16") (pintype "power_in"))
      (node (ref "U9") (pin "4") (pinfunction "G_4") (pintype "passive"))
    )
    (net (code "2") (name "3V3_SBRIO") (class "Default")
      (node (ref "J24") (pin "F8") (pinfunction "F8_F8") (pintype "passive"))
      (node (ref "J26") (pin "1") (pinfunction "1_1") (pintype "passive"))
    )
    (net (code "3") (name "5V") (class "Default")
      (node (ref "C17") (pin "1") (pinfunction "1_1") (pintype "passive"))
      (node (ref "J14") (pin "2") (pinfunction "2_2") (pintype "passive"))
      (node (ref "J15") (pin "2") (pinfunction "2_2") (pintype "passive"))
      (node (ref "J16") (pin "2") (pinfunction "2_2") (pintype "passive"))
      (node (ref "J17") (pin "2") (pinfunction "2_2") (pintype "passive"))
      (node (ref "J18") (pin "2") (pinfunction "2_2") (pintype "passive"))
      (node (ref "J19") (pin "2") (pinfunction "2_2") (pintype "passive"))
      (node (ref "J2") (pin "1") (pinfunction "1_1") (pintype "passive"))
      (node (ref "J20") (pin "2") (pinfunction "2_2") (pintype "passive"))
      (node (ref "J21") (pin "2") (pinfunction "2_2") (pintype "passive"))
      (node (ref "J22") (pin "2") (pinfunction "2_2") (pintype "passive"))
      (node (ref "J23") (pin "2") (pinfunction "2_2") (pintype "passive"))
      (node (ref "R1") (pin "1") (pinfunction "1_1") (pintype "passive"))
      (node (ref "U11") (pin "2") (pinfunction "VIN_2") (pintype "power_in"))
    )
    (net (code "4") (name "5V_C_SERIES") (class "Default")
      (node (ref "C11") (pin "1") (pinfunction "1_1") (pintype "passive"))
      (node (ref "C12") (pin "1") (pinfunction "+_1") (pintype "bidirectional"))
      (node (ref "C13") (pin "1") (pinfunction "1_1") (pintype "passive"))
      (node (ref "J24") (pin "A16") (pinfunction "A16_A16") (pintype "passive"))
      (node (ref "J24") (pin "B15") (pinfunction "B15_B15") (pintype "passive"))
      (node (ref "J29") (pin "19") (pinfunction "19_19") (pintype "passive"))
      (node (ref "L1") (pin "1") (pinfunction "1_1") (pintype "bidirectional"))
    )
    (net (code "5") (name "5V_FILT") (class "Default")
      (node (ref "C14") (pin "1") (pinfunction "1_1") (pintype "passive"))
      (node (ref "C15") (pin "1") (pinfunction "1_1") (pintype "passive"))
      (node (ref "C16") (pin "1") (pinfunction "1_1") (pintype "passive"))
      (node (ref "J1") (pin "4") (pinfunction "4_4") (pintype "bidirectional"))
      (node (ref "L1") (pin "2") (pinfunction "2_2") (pintype "bidirectional"))
    )
    (net (code "6") (name "5V_SBRIO") (class "Default")
      (node (ref "J24") (pin "F10") (pinfunction "F10_F10") (pintype "passive"))
      (node (ref "J24") (pin "F11") (pinfunction "F11_F11") (pintype "passive"))
      (node (ref "J24") (pin "F12") (pinfunction "F12_F12") (pintype "passive"))
      (node (ref "J24") (pin "F9") (pinfunction "F9_F9") (pintype "passive"))
      (node (ref "J26") (pin "3") (pinfunction "3_3") (pintype "passive"))
      (node (ref "J26") (pin "5") (pinfunction "5_5") (pintype "passive"))
    )
    (net (code "7") (name "AGND") (class "Default")
      (node (ref "J10") (pin "8") (pinfunction "8_8") (pintype "passive"))
      (node (ref "J11") (pin "8") (pinfunction "8_8") (pintype "passive"))
      (node (ref "J12") (pin "8") (pinfunction "8_8") (pintype "passive"))
      (node (ref "J13") (pin "8") (pinfunction "8_8") (pintype "passive"))
      (node (ref "J3") (pin "10") (pinfunction "10_10") (pintype "passive"))
      (node (ref "J3") (pin "11") (pinfunction "11_11") (pintype "passive"))
      (node (ref "J3") (pin "14") (pinfunction "14_14") (pintype "passive"))
      (node (ref "J3") (pin "15") (pinfunction "15_15") (pintype "passive"))
      (node (ref "J3") (pin "18") (pinfunction "18_18") (pintype "passive"))
      (node (ref "J3") (pin "19") (pinfunction "19_19") (pintype "passive"))
      (node (ref "J3") (pin "2") (pinfunction "2_2") (pintype "passive"))
      (node (ref "J3") (pin "3") (pinfunction "3_3") (pintype "passive"))
      (node (ref "J3") (pin "6") (pinfunction "6_6") (pintype "passive"))
      (node (ref "J3") (pin "7") (pinfunction "7_7") (pintype "passive"))
      (node (ref "J4") (pin "8") (pinfunction "8_8") (pintype "passive"))
      (node (ref "J5") (pin "8") (pinfunction "8_8") (pintype "passive"))
      (node (ref "J6") (pin "8") (pinfunction "8_8") (pintype "passive"))
      (node (ref "J7") (pin "8") (pinfunction "8_8") (pintype "passive"))
      (node (ref "J8") (pin "8") (pinfunction "8_8") (pintype "passive"))
      (node (ref "J9") (pin "8") (pinfunction "8_8") (pintype "passive"))
    )
    (net (code "8") (name "ANA1") (class "Default")
      (node (ref "J13") (pin "7") (pinfunction "7_7") (pintype "passive"))
      (node (ref "J3") (pin "20") (pinfunction "20_20") (pintype "passive"))
    )
    (net (code "9") (name "ANA2") (class "Default")
      (node (ref "J3") (pin "16") (pinfunction "16_16") (pintype "passive"))
      (node (ref "J8") (pin "7") (pinfunction "7_7") (pintype "passive"))
    )
    (net (code "10") (name "ANA3") (class "Default")
      (node (ref "J12") (pin "7") (pinfunction "7_7") (pintype "passive"))
      (node (ref "J3") (pin "12") (pinfunction "12_12") (pintype "passive"))
    )
    (net (code "11") (name "ANA4") (class "Default")
      (node (ref "J3") (pin "8") (pinfunction "8_8") (pintype "passive"))
      (node (ref "J7") (pin "7") (pinfunction "7_7") (pintype "passive"))
    )
    (net (code "12") (name "ANA5") (class "Default")
      (node (ref "J11") (pin "7") (pinfunction "7_7") (pintype "passive"))
      (node (ref "J3") (pin "4") (pinfunction "4_4") (pintype "passive"))
    )
    (net (code "13") (name "ANA6") (class "Default")
      (node (ref "J3") (pin "1") (pinfunction "1_1") (pintype "passive"))
      (node (ref "J6") (pin "7") (pinfunction "7_7") (pintype "passive"))
    )
    (net (code "14") (name "ANA7") (class "Default")
      (node (ref "J10") (pin "7") (pinfunction "7_7") (pintype "passive"))
      (node (ref "J3") (pin "5") (pinfunction "5_5") (pintype "passive"))
    )
    (net (code "15") (name "ANA8") (class "Default")
      (node (ref "J3") (pin "9") (pinfunction "9_9") (pintype "passive"))
      (node (ref "J5") (pin "7") (pinfunction "7_7") (pintype "passive"))
    )
    (net (code "16") (name "ANA9") (class "Default")
      (node (ref "J3") (pin "13") (pinfunction "13_13") (pintype "passive"))
      (node (ref "J9") (pin "7") (pinfunction "7_7") (pintype "passive"))
    )
    (net (code "17") (name "ANA10") (class "Default")
      (node (ref "J3") (pin "17") (pinfunction "17_17") (pintype "passive"))
      (node (ref "J4") (pin "7") (pinfunction "7_7") (pintype "passive"))
    )
    (net (code "18") (name "A_M1") (class "Default")
      (node (ref "RN10") (pin "4") (pinfunction "4_4") (pintype "passive"))
      (node (ref "U10") (pin "11") (pinfunction "3Y_11") (pintype "output"))
    )
    (net (code "19") (name "A_M1_N") (class "Default")
      (node (ref "J23") (pin "9") (pinfunction "9_9") (pintype "passive"))
      (node (ref "U10") (pin "9") (pinfunction "3B_9") (pintype "input"))
    )
    (net (code "20") (name "A_M1_P") (class "Default")
      (node (ref "J23") (pin "10") (pinfunction "10_10") (pintype "passive"))
      (node (ref "U10") (pin "10") (pinfunction "3A_10") (pintype "input"))
    )
    (net (code "21") (name "A_M2") (class "Default")
      (node (ref "RN5") (pin "4") (pinfunction "4_4") (pintype "passive"))
      (node (ref "U5") (pin "11") (pinfunction "3Y_11") (pintype "output"))
    )
    (net (code "22") (name "A_M2_N") (class "Default")
      (node (ref "J18") (pin "9") (pinfunction "9_9") (pintype "passive"))
      (node (ref "U5") (pin "9") (pinfunction "3B_9") (pintype "input"))
    )
    (net (code "23") (name "A_M2_P") (class "Default")
      (node (ref "J18") (pin "10") (pinfunction "10_10") (pintype "passive"))
      (node (ref "U5") (pin "10") (pinfunction "3A_10") (pintype "input"))
    )
    (net (code "24") (name "A_M3") (class "Default")
      (node (ref "RN9") (pin "4") (pinfunction "4_4") (pintype "passive"))
      (node (ref "U9") (pin "11") (pinfunction "3Y_11") (pintype "output"))
    )
    (net (code "25") (name "A_M3_N") (class "Default")
      (node (ref "J22") (pin "9") (pinfunction "9_9") (pintype "passive"))
      (node (ref "U9") (pin "9") (pinfunction "3B_9") (pintype "input"))
    )
    (net (code "26") (name "A_M3_P") (class "Default")
      (node (ref "J22") (pin "10") (pinfunction "10_10") (pintype "passive"))
      (node (ref "U9") (pin "10") (pinfunction "3A_10") (pintype "input"))
    )
    (net (code "27") (name "A_M4") (class "Default")
      (node (ref "RN4") (pin "4") (pinfunction "4_4") (pintype "passive"))
      (node (ref "U4") (pin "11") (pinfunction "3Y_11") (pintype "output"))
    )
    (net (code "28") (name "A_M4_N") (class "Default")
      (node (ref "J17") (pin "9") (pinfunction "9_9") (pintype "passive"))
      (node (ref "U4") (pin "9") (pinfunction "3B_9") (pintype "input"))
    )
    (net (code "29") (name "A_M4_P") (class "Default")
      (node (ref "J17") (pin "10") (pinfunction "10_10") (pintype "passive"))
      (node (ref "U4") (pin "10") (pinfunction "3A_10") (pintype "input"))
    )
    (net (code "30") (name "A_M5") (class "Default")
      (node (ref "RN8") (pin "4") (pinfunction "4_4") (pintype "passive"))
      (node (ref "U8") (pin "11") (pinfunction "3Y_11") (pintype "output"))
    )
    (net (code "31") (name "A_M5_N") (class "Default")
      (node (ref "J21") (pin "9") (pinfunction "9_9") (pintype "passive"))
      (node (ref "U8") (pin "9") (pinfunction "3B_9") (pintype "input"))
    )
    (net (code "32") (name "A_M5_P") (class "Default")
      (node (ref "J21") (pin "10") (pinfunction "10_10") (pintype "passive"))
      (node (ref "U8") (pin "10") (pinfunction "3A_10") (pintype "input"))
    )
    (net (code "33") (name "A_M6") (class "Default")
      (node (ref "RN3") (pin "4") (pinfunction "4_4") (pintype "passive"))
      (node (ref "U3") (pin "11") (pinfunction "3Y_11") (pintype "output"))
    )
    (net (code "34") (name "A_M6_N") (class "Default")
      (node (ref "J16") (pin "9") (pinfunction "9_9") (pintype "passive"))
      (node (ref "U3") (pin "9") (pinfunction "3B_9") (pintype "input"))
    )
    (net (code "35") (name "A_M6_P") (class "Default")
      (node (ref "J16") (pin "10") (pinfunction "10_10") (pintype "passive"))
      (node (ref "U3") (pin "10") (pinfunction "3A_10") (pintype "input"))
    )
    (net (code "36") (name "A_M7") (class "Default")
      (node (ref "RN7") (pin "4") (pinfunction "4_4") (pintype "passive"))
      (node (ref "U7") (pin "11") (pinfunction "3Y_11") (pintype "output"))
    )
    (net (code "37") (name "A_M7_N") (class "Default")
      (node (ref "J20") (pin "9") (pinfunction "9_9") (pintype "passive"))
      (node (ref "U7") (pin "9") (pinfunction "3B_9") (pintype "input"))
    )
    (net (code "38") (name "A_M7_P") (class "Default")
      (node (ref "J20") (pin "10") (pinfunction "10_10") (pintype "passive"))
      (node (ref "U7") (pin "10") (pinfunction "3A_10") (pintype "input"))
    )
    (net (code "39") (name "A_M8") (class "Default")
      (node (ref "RN2") (pin "4") (pinfunction "4_4") (pintype "passive"))
      (node (ref "U2") (pin "11") (pinfunction "3Y_11") (pintype "output"))
    )
    (net (code "40") (name "A_M8_N") (class "Default")
      (node (ref "J15") (pin "9") (pinfunction "9_9") (pintype "passive"))
      (node (ref "U2") (pin "9") (pinfunction "3B_9") (pintype "input"))
    )
    (net (code "41") (name "A_M8_P") (class "Default")
      (node (ref "J15") (pin "10") (pinfunction "10_10") (pintype "passive"))
      (node (ref "U2") (pin "10") (pinfunction "3A_10") (pintype "input"))
    )
    (net (code "42") (name "A_M9") (class "Default")
      (node (ref "RN6") (pin "4") (pinfunction "4_4") (pintype "passive"))
      (node (ref "U6") (pin "11") (pinfunction "3Y_11") (pintype "output"))
    )
    (net (code "43") (name "A_M9_N") (class "Default")
      (node (ref "J19") (pin "9") (pinfunction "9_9") (pintype "passive"))
      (node (ref "U6") (pin "9") (pinfunction "3B_9") (pintype "input"))
    )
    (net (code "44") (name "A_M9_P") (class "Default")
      (node (ref "J19") (pin "10") (pinfunction "10_10") (pintype "passive"))
      (node (ref "U6") (pin "10") (pinfunction "3A_10") (pintype "input"))
    )
    (net (code "45") (name "A_M10") (class "Default")
      (node (ref "RN1") (pin "4") (pinfunction "4_4") (pintype "passive"))
      (node (ref "U1") (pin "11") (pinfunction "3Y_11") (pintype "output"))
    )
    (net (code "46") (name "A_M10_N") (class "Default")
      (node (ref "J14") (pin "9") (pinfunction "9_9") (pintype "passive"))
      (node (ref "U1") (pin "9") (pinfunction "3B_9") (pintype "input"))
    )
    (net (code "47") (name "A_M10_P") (class "Default")
      (node (ref "J14") (pin "10") (pinfunction "10_10") (pintype "passive"))
      (node (ref "U1") (pin "10") (pinfunction "3A_10") (pintype "input"))
    )
    (net (code "48") (name "B_M1") (class "Default")
      (node (ref "RN10") (pin "3") (pinfunction "3_3") (pintype "passive"))
      (node (ref "U10") (pin "13") (pinfunction "4Y_13") (pintype "output"))
    )
    (net (code "49") (name "B_M1_N") (class "Default")
      (node (ref "J23") (pin "7") (pinfunction "7_7") (pintype "passive"))
      (node (ref "U10") (pin "15") (pinfunction "4B_15") (pintype "input"))
    )
    (net (code "50") (name "B_M1_P") (class "Default")
      (node (ref "J23") (pin "8") (pinfunction "8_8") (pintype "passive"))
      (node (ref "U10") (pin "14") (pinfunction "4A_14") (pintype "input"))
    )
    (net (code "51") (name "B_M2") (class "Default")
      (node (ref "RN5") (pin "3") (pinfunction "3_3") (pintype "passive"))
      (node (ref "U5") (pin "13") (pinfunction "4Y_13") (pintype "output"))
    )
    (net (code "52") (name "B_M2_N") (class "Default")
      (node (ref "J18") (pin "7") (pinfunction "7_7") (pintype "passive"))
      (node (ref "U5") (pin "15") (pinfunction "4B_15") (pintype "input"))
    )
    (net (code "53") (name "B_M2_P") (class "Default")
      (node (ref "J18") (pin "8") (pinfunction "8_8") (pintype "passive"))
      (node (ref "U5") (pin "14") (pinfunction "4A_14") (pintype "input"))
    )
    (net (code "54") (name "B_M3") (class "Default")
      (node (ref "RN9") (pin "3") (pinfunction "3_3") (pintype "passive"))
      (node (ref "U9") (pin "13") (pinfunction "4Y_13") (pintype "output"))
    )
    (net (code "55") (name "B_M3_N") (class "Default")
      (node (ref "J22") (pin "7") (pinfunction "7_7") (pintype "passive"))
      (node (ref "U9") (pin "15") (pinfunction "4B_15") (pintype "input"))
    )
    (net (code "56") (name "B_M3_P") (class "Default")
      (node (ref "J22") (pin "8") (pinfunction "8_8") (pintype "passive"))
      (node (ref "U9") (pin "14") (pinfunction "4A_14") (pintype "input"))
    )
    (net (code "57") (name "B_M4") (class "Default")
      (node (ref "RN4") (pin "3") (pinfunction "3_3") (pintype "passive"))
      (node (ref "U4") (pin "13") (pinfunction "4Y_13") (pintype "output"))
    )
    (net (code "58") (name "B_M4_N") (class "Default")
      (node (ref "J17") (pin "7") (pinfunction "7_7") (pintype "passive"))
      (node (ref "U4") (pin "15") (pinfunction "4B_15") (pintype "input"))
    )
    (net (code "59") (name "B_M4_P") (class "Default")
      (node (ref "J17") (pin "8") (pinfunction "8_8") (pintype "passive"))
      (node (ref "U4") (pin "14") (pinfunction "4A_14") (pintype "input"))
    )
    (net (code "60") (name "B_M5") (class "Default")
      (node (ref "RN8") (pin "3") (pinfunction "3_3") (pintype "passive"))
      (node (ref "U8") (pin "13") (pinfunction "4Y_13") (pintype "output"))
    )
    (net (code "61") (name "B_M5_N") (class "Default")
      (node (ref "J21") (pin "7") (pinfunction "7_7") (pintype "passive"))
      (node (ref "U8") (pin "15") (pinfunction "4B_15") (pintype "input"))
    )
    (net (code "62") (name "B_M5_P") (class "Default")
      (node (ref "J21") (pin "8") (pinfunction "8_8") (pintype "passive"))
      (node (ref "U8") (pin "14") (pinfunction "4A_14") (pintype "input"))
    )
    (net (code "63") (name "B_M6") (class "Default")
      (node (ref "RN3") (pin "3") (pinfunction "3_3") (pintype "passive"))
      (node (ref "U3") (pin "13") (pinfunction "4Y_13") (pintype "output"))
    )
    (net (code "64") (name "B_M6_N") (class "Default")
      (node (ref "J16") (pin "7") (pinfunction "7_7") (pintype "passive"))
      (node (ref "U3") (pin "15") (pinfunction "4B_15") (pintype "input"))
    )
    (net (code "65") (name "B_M6_P") (class "Default")
      (node (ref "J16") (pin "8") (pinfunction "8_8") (pintype "passive"))
      (node (ref "U3") (pin "14") (pinfunction "4A_14") (pintype "input"))
    )
    (net (code "66") (name "B_M7") (class "Default")
      (node (ref "RN7") (pin "3") (pinfunction "3_3") (pintype "passive"))
      (node (ref "U7") (pin "13") (pinfunction "4Y_13") (pintype "output"))
    )
    (net (code "67") (name "B_M7_N") (class "Default")
      (node (ref "J20") (pin "7") (pinfunction "7_7") (pintype "passive"))
      (node (ref "U7") (pin "15") (pinfunction "4B_15") (pintype "input"))
    )
    (net (code "68") (name "B_M7_P") (class "Default")
      (node (ref "J20") (pin "8") (pinfunction "8_8") (pintype "passive"))
      (node (ref "U7") (pin "14") (pinfunction "4A_14") (pintype "input"))
    )
    (net (code "69") (name "B_M8") (class "Default")
      (node (ref "RN2") (pin "3") (pinfunction "3_3") (pintype "passive"))
      (node (ref "U2") (pin "13") (pinfunction "4Y_13") (pintype "output"))
    )
    (net (code "70") (name "B_M8_N") (class "Default")
      (node (ref "J15") (pin "7") (pinfunction "7_7") (pintype "passive"))
      (node (ref "U2") (pin "15") (pinfunction "4B_15") (pintype "input"))
    )
    (net (code "71") (name "B_M8_P") (class "Default")
      (node (ref "J15") (pin "8") (pinfunction "8_8") (pintype "passive"))
      (node (ref "U2") (pin "14") (pinfunction "4A_14") (pintype "input"))
    )
    (net (code "72") (name "B_M9") (class "Default")
      (node (ref "RN6") (pin "3") (pinfunction "3_3") (pintype "passive"))
      (node (ref "U6") (pin "13") (pinfunction "4Y_13") (pintype "output"))
    )
    (net (code "73") (name "B_M9_N") (class "Default")
      (node (ref "J19") (pin "7") (pinfunction "7_7") (pintype "passive"))
      (node (ref "U6") (pin "15") (pinfunction "4B_15") (pintype "input"))
    )
    (net (code "74") (name "B_M9_P") (class "Default")
      (node (ref "J19") (pin "8") (pinfunction "8_8") (pintype "passive"))
      (node (ref "U6") (pin "14") (pinfunction "4A_14") (pintype "input"))
    )
    (net (code "75") (name "B_M10") (class "Default")
      (node (ref "RN1") (pin "3") (pinfunction "3_3") (pintype "passive"))
      (node (ref "U1") (pin "13") (pinfunction "4Y_13") (pintype "output"))
    )
    (net (code "76") (name "B_M10_N") (class "Default")
      (node (ref "J14") (pin "7") (pinfunction "7_7") (pintype "passive"))
      (node (ref "U1") (pin "15") (pinfunction "4B_15") (pintype "input"))
    )
    (net (code "77") (name "B_M10_P") (class "Default")
      (node (ref "J14") (pin "8") (pinfunction "8_8") (pintype "passive"))
      (node (ref "U1") (pin "14") (pinfunction "4A_14") (pintype "input"))
    )
    (net (code "78") (name "CVRT#_DIO3[1]") (class "Default")
      (node (ref "J1") (pin "9") (pinfunction "9_9") (pintype "bidirectional"))
      (node (ref "J24") (pin "D8") (pinfunction "D8_D8") (pintype "passive"))
    )
    (net (code "79") (name "DIO0") (class "Default")
      (node (ref "J24") (pin "F38") (pinfunction "F38_F38") (pintype "passive"))
      (node (ref "RN9") (pin "5") (pinfunction "5_5") (pintype "passive"))
    )
    (net (code "80") (name "DIO1") (class "Default")
      (node (ref "J24") (pin "F36") (pinfunction "F36_F36") (pintype "passive"))
      (node (ref "RN9") (pin "6") (pinfunction "6_6") (pintype "passive"))
    )
    (net (code "81") (name "DIO2") (class "Default")
      (node (ref "J24") (pin "F35") (pinfunction "F35_F35") (pintype "passive"))
      (node (ref "RN9") (pin "7") (pinfunction "7_7") (pintype "passive"))
    )
    (net (code "82") (name "DIO3") (class "Default")
      (node (ref "J24") (pin "F33") (pinfunction "F33_F33") (pintype "passive"))
      (node (ref "RN9") (pin "8") (pinfunction "8_8") (pintype "passive"))
    )
    (net (code "83") (name "DIO4") (class "Default")
      (node (ref "J24") (pin "F32") (pinfunction "F32_F32") (pintype "passive"))
      (node (ref "RN8") (pin "5") (pinfunction "5_5") (pintype "passive"))
    )
    (net (code "84") (name "DIO5") (class "Default")
      (node (ref "J24") (pin "F30") (pinfunction "F30_F30") (pintype "passive"))
      (node (ref "RN8") (pin "6") (pinfunction "6_6") (pintype "passive"))
    )
    (net (code "85") (name "DIO6") (class "Default")
      (node (ref "J24") (pin "F29") (pinfunction "F29_F29") (pintype "passive"))
      (node (ref "RN8") (pin "7") (pinfunction "7_7") (pintype "passive"))
    )
    (net (code "86") (name "DIO7") (class "Default")
      (node (ref "J24") (pin "F27") (pinfunction "F27_F27") (pintype "passive"))
      (node (ref "RN8") (pin "8") (pinfunction "8_8") (pintype "passive"))
    )
    (net (code "87") (name "DIO8") (class "Default")
      (node (ref "J24") (pin "F26") (pinfunction "F26_F26") (pintype "passive"))
      (node (ref "RN7") (pin "5") (pinfunction "5_5") (pintype "passive"))
    )
    (net (code "88") (name "DIO9") (class "Default")
      (node (ref "J24") (pin "F24") (pinfunction "F24_F24") (pintype "passive"))
      (node (ref "RN7") (pin "6") (pinfunction "6_6") (pintype "passive"))
    )
    (net (code "89") (name "DIO10") (class "Default")
      (node (ref "J24") (pin "F23") (pinfunction "F23_F23") (pintype "passive"))
      (node (ref "RN7") (pin "7") (pinfunction "7_7") (pintype "passive"))
    )
    (net (code "90") (name "DIO11") (class "Default")
      (node (ref "J24") (pin "F21") (pinfunction "F21_F21") (pintype "passive"))
      (node (ref "RN7") (pin "8") (pinfunction "8_8") (pintype "passive"))
    )
    (net (code "91") (name "DIO12") (class "Default")
      (node (ref "J24") (pin "F20") (pinfunction "F20_F20") (pintype "passive"))
      (node (ref "RN6") (pin "5") (pinfunction "5_5") (pintype "passive"))
    )
    (net (code "92") (name "DIO13") (class "Default")
      (node (ref "J24") (pin "F18") (pinfunction "F18_F18") (pintype "passive"))
      (node (ref "RN6") (pin "6") (pinfunction "6_6") (pintype "passive"))
    )
    (net (code "93") (name "DIO14") (class "Default")
      (node (ref "J24") (pin "F17") (pinfunction "F17_F17") (pintype "passive"))
      (node (ref "RN6") (pin "7") (pinfunction "7_7") (pintype "passive"))
    )
    (net (code "94") (name "DIO15") (class "Default")
      (node (ref "J24") (pin "F15") (pinfunction "F15_F15") (pintype "passive"))
      (node (ref "RN6") (pin "8") (pinfunction "8_8") (pintype "passive"))
    )
    (net (code "95") (name "DIO16") (class "Default")
      (node (ref "J24") (pin "C39") (pinfunction "C39_C39") (pintype "passive"))
      (node (ref "RN10") (pin "6") (pinfunction "6_6") (pintype "passive"))
    )
    (net (code "96") (name "DIO17") (class "Default")
      (node (ref "J24") (pin "C38") (pinfunction "C38_C38") (pintype "passive"))
      (node (ref "RN10") (pin "7") (pinfunction "7_7") (pintype "passive"))
    )
    (net (code "97") (name "DIO18") (class "Default")
      (node (ref "J24") (pin "C36") (pinfunction "C36_C36") (pintype "passive"))
    )
    (net (code "98") (name "DIO19") (class "Default")
      (node (ref "J24") (pin "C35") (pinfunction "C35_C35") (pintype "passive"))
    )
    (net (code "99") (name "DIO20") (class "Default")
      (node (ref "J24") (pin "C33") (pinfunction "C33_C33") (pintype "passive"))
    )
    (net (code "100") (name "DIO21") (class "Default")
      (node (ref "J24") (pin "C32") (pinfunction "C32_C32") (pintype "passive"))
      (node (ref "J29") (pin "15") (pinfunction "15_15") (pintype "passive"))
    )
    (net (code "101") (name "DIO22") (class "Default")
      (node (ref "J24") (pin "C30") (pinfunction "C30_C30") (pintype "passive"))
      (node (ref "J29") (pin "7") (pinfunction "7_7") (pintype "passive"))
    )
    (net (code "102") (name "DIO23") (class "Default")
      (node (ref "J24") (pin "C29") (pinfunction "C29_C29") (pintype "passive"))
      (node (ref "J29") (pin "3") (pinfunction "3_3") (pintype "passive"))
    )
    (net (code "103") (name "DIO24") (class "Default")
      (node (ref "J24") (pin "C27") (pinfunction "C27_C27") (pintype "passive"))
      (node (ref "J28") (pin "15") (pinfunction "15_15") (pintype "passive"))
    )
    (net (code "104") (name "DIO25") (class "Default")
      (node (ref "J24") (pin "C26") (pinfunction "C26_C26") (pintype "passive"))
      (node (ref "J28") (pin "11") (pinfunction "11_11") (pintype "passive"))
    )
    (net (code "105") (name "DIO26") (class "Default")
      (node (ref "J24") (pin "C24") (pinfunction "C24_C24") (pintype "passive"))
      (node (ref "J28") (pin "3") (pinfunction "3_3") (pintype "passive"))
    )
    (net (code "106") (name "DIO27") (class "Default")
      (node (ref "J24") (pin "C23") (pinfunction "C23_C23") (pintype "passive"))
      (node (ref "J27") (pin "19") (pinfunction "19_19") (pintype "passive"))
    )
    (net (code "107") (name "DIO28") (class "Default")
      (node (ref "J24") (pin "C21") (pinfunction "C21_C21") (pintype "passive"))
      (node (ref "J27") (pin "11") (pinfunction "11_11") (pintype "passive"))
    )
    (net (code "108") (name "DIO29") (class "Default")
      (node (ref "J24") (pin "C20") (pinfunction "C20_C20") (pintype "passive"))
      (node (ref "J27") (pin "7") (pinfunction "7_7") (pintype "passive"))
    )
    (net (code "109") (name "DIO30") (class "Default")
      (node (ref "J24") (pin "C18") (pinfunction "C18_C18") (pintype "passive"))
      (node (ref "J26") (pin "15") (pinfunction "15_15") (pintype "passive"))
    )
    (net (code "110") (name "DIO31") (class "Default")
      (node (ref "J24") (pin "C17") (pinfunction "C17_C17") (pintype "passive"))
      (node (ref "J26") (pin "11") (pinfunction "11_11") (pintype "passive"))
    )
    (net (code "111") (name "DIO32") (class "Default")
      (node (ref "J24") (pin "E37") (pinfunction "E37_E37") (pintype "passive"))
      (node (ref "RN4") (pin "5") (pinfunction "5_5") (pintype "passive"))
    )
    (net (code "112") (name "DIO33") (class "Default")
      (node (ref "J24") (pin "E36") (pinfunction "E36_E36") (pintype "passive"))
      (node (ref "RN4") (pin "6") (pinfunction "6_6") (pintype "passive"))
    )
    (net (code "113") (name "DIO34") (class "Default")
      (node (ref "J24") (pin "E34") (pinfunction "E34_E34") (pintype "passive"))
      (node (ref "RN4") (pin "7") (pinfunction "7_7") (pintype "passive"))
    )
    (net (code "114") (name "DIO35") (class "Default")
      (node (ref "J24") (pin "E33") (pinfunction "E33_E33") (pintype "passive"))
      (node (ref "RN4") (pin "8") (pinfunction "8_8") (pintype "passive"))
    )
    (net (code "115") (name "DIO36") (class "Default")
      (node (ref "J24") (pin "E31") (pinfunction "E31_E31") (pintype "passive"))
      (node (ref "RN3") (pin "5") (pinfunction "5_5") (pintype "passive"))
    )
    (net (code "116") (name "DIO37") (class "Default")
      (node (ref "J24") (pin "E30") (pinfunction "E30_E30") (pintype "passive"))
      (node (ref "RN3") (pin "6") (pinfunction "6_6") (pintype "passive"))
    )
    (net (code "117") (name "DIO38") (class "Default")
      (node (ref "J24") (pin "E28") (pinfunction "E28_E28") (pintype "passive"))
      (node (ref "RN3") (pin "7") (pinfunction "7_7") (pintype "passive"))
    )
    (net (code "118") (name "DIO39") (class "Default")
      (node (ref "J24") (pin "E27") (pinfunction "E27_E27") (pintype "passive"))
      (node (ref "RN3") (pin "8") (pinfunction "8_8") (pintype "passive"))
    )
    (net (code "119") (name "DIO40") (class "Default")
      (node (ref "J24") (pin "E25") (pinfunction "E25_E25") (pintype "passive"))
      (node (ref "RN2") (pin "5") (pinfunction "5_5") (pintype "passive"))
    )
    (net (code "120") (name "DIO41") (class "Default")
      (node (ref "J24") (pin "E24") (pinfunction "E24_E24") (pintype "passive"))
      (node (ref "RN2") (pin "6") (pinfunction "6_6") (pintype "passive"))
    )
    (net (code "121") (name "DIO42") (class "Default")
      (node (ref "J24") (pin "E22") (pinfunction "E22_E22") (pintype "passive"))
      (node (ref "RN2") (pin "7") (pinfunction "7_7") (pintype "passive"))
    )
    (net (code "122") (name "DIO43") (class "Default")
      (node (ref "J24") (pin "E21") (pinfunction "E21_E21") (pintype "passive"))
      (node (ref "RN2") (pin "8") (pinfunction "8_8") (pintype "passive"))
    )
    (net (code "123") (name "DIO44") (class "Default")
      (node (ref "J24") (pin "E19") (pinfunction "E19_E19") (pintype "passive"))
      (node (ref "RN1") (pin "5") (pinfunction "5_5") (pintype "passive"))
    )
    (net (code "124") (name "DIO45") (class "Default")
      (node (ref "J24") (pin "E18") (pinfunction "E18_E18") (pintype "passive"))
      (node (ref "RN1") (pin "6") (pinfunction "6_6") (pintype "passive"))
    )
    (net (code "125") (name "DIO46") (class "Default")
      (node (ref "J24") (pin "E16") (pinfunction "E16_E16") (pintype "passive"))
      (node (ref "RN1") (pin "7") (pinfunction "7_7") (pintype "passive"))
    )
    (net (code "126") (name "DIO47") (class "Default")
      (node (ref "J24") (pin "E15") (pinfunction "E15_E15") (pintype "passive"))
      (node (ref "RN1") (pin "8") (pinfunction "8_8") (pintype "passive"))
    )
    (net (code "127") (name "DIO48") (class "Default")
      (node (ref "J24") (pin "B39") (pinfunction "B39_B39") (pintype "passive"))
      (node (ref "RN10") (pin "5") (pinfunction "5_5") (pintype "passive"))
    )
    (net (code "128") (name "DIO49") (class "Default")
      (node (ref "J24") (pin "B37") (pinfunction "B37_B37") (pintype "passive"))
      (node (ref "RN10") (pin "8") (pinfunction "8_8") (pintype "passive"))
    )
    (net (code "129") (name "DIO50") (class "Default")
      (node (ref "J24") (pin "B36") (pinfunction "B36_B36") (pintype "passive"))
    )
    (net (code "130") (name "DIO51") (class "Default")
      (node (ref "J24") (pin "B34") (pinfunction "B34_B34") (pintype "passive"))
    )
    (net (code "131") (name "DIO52") (class "Default")
      (node (ref "J24") (pin "B33") (pinfunction "B33_B33") (pintype "passive"))
      (node (ref "J29") (pin "17") (pinfunction "17_17") (pintype "passive"))
    )
    (net (code "132") (name "DIO53") (class "Default")
      (node (ref "J24") (pin "B31") (pinfunction "B31_B31") (pintype "passive"))
      (node (ref "J29") (pin "11") (pinfunction "11_11") (pintype "passive"))
    )
    (net (code "133") (name "DIO54") (class "Default")
      (node (ref "J24") (pin "B30") (pinfunction "B30_B30") (pintype "passive"))
      (node (ref "J29") (pin "5") (pinfunction "5_5") (pintype "passive"))
    )
    (net (code "134") (name "DIO55") (class "Default")
      (node (ref "J24") (pin "B28") (pinfunction "B28_B28") (pintype "passive"))
      (node (ref "J28") (pin "19") (pinfunction "19_19") (pintype "passive"))
    )
    (net (code "135") (name "DIO56") (class "Default")
      (node (ref "J24") (pin "B27") (pinfunction "B27_B27") (pintype "passive"))
      (node (ref "J28") (pin "13") (pinfunction "13_13") (pintype "passive"))
    )
    (net (code "136") (name "DIO57") (class "Default")
      (node (ref "J24") (pin "B25") (pinfunction "B25_B25") (pintype "passive"))
      (node (ref "J28") (pin "7") (pinfunction "7_7") (pintype "passive"))
    )
    (net (code "137") (name "DIO58") (class "Default")
      (node (ref "J24") (pin "B24") (pinfunction "B24_B24") (pintype "passive"))
      (node (ref "J28") (pin "1") (pinfunction "1_1") (pintype "passive"))
    )
    (net (code "138") (name "DIO59") (class "Default")
      (node (ref "J24") (pin "B22") (pinfunction "B22_B22") (pintype "passive"))
      (node (ref "J27") (pin "15") (pinfunction "15_15") (pintype "passive"))
    )
    (net (code "139") (name "DIO60") (class "Default")
      (node (ref "J24") (pin "B21") (pinfunction "B21_B21") (pintype "passive"))
      (node (ref "J27") (pin "9") (pinfunction "9_9") (pintype "passive"))
    )
    (net (code "140") (name "DIO61") (class "Default")
      (node (ref "J24") (pin "B19") (pinfunction "B19_B19") (pintype "passive"))
      (node (ref "J27") (pin "3") (pinfunction "3_3") (pintype "passive"))
    )
    (net (code "141") (name "DIO62") (class "Default")
      (node (ref "J24") (pin "B18") (pinfunction "B18_B18") (pintype "passive"))
      (node (ref "J26") (pin "17") (pinfunction "17_17") (pintype "passive"))
    )
    (net (code "142") (name "DIO64") (class "Default")
      (node (ref "J24") (pin "D38") (pinfunction "D38_D38") (pintype "passive"))
    )
    (net (code "143") (name "DIO65") (class "Default")
      (node (ref "J24") (pin "D37") (pinfunction "D37_D37") (pintype "passive"))
    )
    (net (code "144") (name "DIO66") (class "Default")
      (node (ref "J24") (pin "D35") (pinfunction "D35_D35") (pintype "passive"))
    )
    (net (code "145") (name "DIO67") (class "Default")
      (node (ref "J24") (pin "D34") (pinfunction "D34_D34") (pintype "passive"))
    )
    (net (code "146") (name "DIO68") (class "Default")
      (node (ref "J24") (pin "D32") (pinfunction "D32_D32") (pintype "passive"))
    )
    (net (code "147") (name "DIO69") (class "Default")
      (node (ref "J24") (pin "D31") (pinfunction "D31_D31") (pintype "passive"))
    )
    (net (code "148") (name "DIO70") (class "Default")
      (node (ref "J24") (pin "D29") (pinfunction "D29_D29") (pintype "passive"))
    )
    (net (code "149") (name "DIO71") (class "Default")
      (node (ref "J24") (pin "D28") (pinfunction "D28_D28") (pintype "passive"))
    )
    (net (code "150") (name "DIO72") (class "Default")
      (node (ref "J24") (pin "D26") (pinfunction "D26_D26") (pintype "passive"))
    )
    (net (code "151") (name "DIO73") (class "Default")
      (node (ref "J24") (pin "D25") (pinfunction "D25_D25") (pintype "passive"))
    )
    (net (code "152") (name "DIO74") (class "Default")
      (node (ref "J24") (pin "D23") (pinfunction "D23_D23") (pintype "passive"))
    )
    (net (code "153") (name "DIO75") (class "Default")
      (node (ref "J24") (pin "D22") (pinfunction "D22_D22") (pintype "passive"))
    )
    (net (code "154") (name "DIO76") (class "Default")
      (node (ref "J24") (pin "D20") (pinfunction "D20_D20") (pintype "passive"))
    )
    (net (code "155") (name "DIO77") (class "Default")
      (node (ref "J24") (pin "D19") (pinfunction "D19_D19") (pintype "passive"))
      (node (ref "J26") (pin "19") (pinfunction "19_19") (pintype "passive"))
    )
    (net (code "156") (name "DIO78") (class "Default")
      (node (ref "J24") (pin "D17") (pinfunction "D17_D17") (pintype "passive"))
      (node (ref "J26") (pin "9") (pinfunction "9_9") (pintype "passive"))
    )
    (net (code "157") (name "DIO79") (class "Default")
      (node (ref "J24") (pin "D16") (pinfunction "D16_D16") (pintype "passive"))
      (node (ref "J26") (pin "7") (pinfunction "7_7") (pintype "passive"))
    )
    (net (code "158") (name "DIO80") (class "Default")
      (node (ref "J24") (pin "A40") (pinfunction "A40_A40") (pintype "passive"))
      (node (ref "RN5") (pin "7") (pinfunction "7_7") (pintype "passive"))
    )
    (net (code "159") (name "DIO81") (class "Default")
      (node (ref "J24") (pin "A38") (pinfunction "A38_A38") (pintype "passive"))
      (node (ref "RN5") (pin "6") (pinfunction "6_6") (pintype "passive"))
    )
    (net (code "160") (name "DIO82") (class "Default")
      (node (ref "J24") (pin "A37") (pinfunction "A37_A37") (pintype "passive"))
      (node (ref "RN5") (pin "5") (pinfunction "5_5") (pintype "passive"))
    )
    (net (code "161") (name "DIO83") (class "Default")
      (node (ref "J24") (pin "A35") (pinfunction "A35_A35") (pintype "passive"))
      (node (ref "RN5") (pin "8") (pinfunction "8_8") (pintype "passive"))
    )
    (net (code "162") (name "DIO84") (class "Default")
      (node (ref "J24") (pin "A34") (pinfunction "A34_A34") (pintype "passive"))
    )
    (net (code "163") (name "DIO85") (class "Default")
      (node (ref "J24") (pin "A32") (pinfunction "A32_A32") (pintype "passive"))
      (node (ref "J29") (pin "13") (pinfunction "13_13") (pintype "passive"))
    )
    (net (code "164") (name "DIO86") (class "Default")
      (node (ref "J24") (pin "A31") (pinfunction "A31_A31") (pintype "passive"))
      (node (ref "J29") (pin "9") (pinfunction "9_9") (pintype "passive"))
    )
    (net (code "165") (name "DIO87") (class "Default")
      (node (ref "J24") (pin "A29") (pinfunction "A29_A29") (pintype "passive"))
      (node (ref "J29") (pin "1") (pinfunction "1_1") (pintype "passive"))
    )
    (net (code "166") (name "DIO88") (class "Default")
      (node (ref "J24") (pin "A28") (pinfunction "A28_A28") (pintype "passive"))
      (node (ref "J28") (pin "17") (pinfunction "17_17") (pintype "passive"))
    )
    (net (code "167") (name "DIO89") (class "Default")
      (node (ref "J24") (pin "A26") (pinfunction "A26_A26") (pintype "passive"))
      (node (ref "J28") (pin "9") (pinfunction "9_9") (pintype "passive"))
    )
    (net (code "168") (name "DIO90") (class "Default")
      (node (ref "J24") (pin "A25") (pinfunction "A25_A25") (pintype "passive"))
      (node (ref "J28") (pin "5") (pinfunction "5_5") (pintype "passive"))
    )
    (net (code "169") (name "DIO91") (class "Default")
      (node (ref "J24") (pin "A23") (pinfunction "A23_A23") (pintype "passive"))
      (node (ref "J27") (pin "17") (pinfunction "17_17") (pintype "passive"))
    )
    (net (code "170") (name "DIO92") (class "Default")
      (node (ref "J24") (pin "A22") (pinfunction "A22_A22") (pintype "passive"))
      (node (ref "J27") (pin "13") (pinfunction "13_13") (pintype "passive"))
    )
    (net (code "171") (name "DIO93") (class "Default")
      (node (ref "J24") (pin "A20") (pinfunction "A20_A20") (pintype "passive"))
      (node (ref "J27") (pin "5") (pinfunction "5_5") (pintype "passive"))
    )
    (net (code "172") (name "DIO94") (class "Default")
      (node (ref "J24") (pin "A19") (pinfunction "A19_A19") (pintype "passive"))
      (node (ref "J27") (pin "1") (pinfunction "1_1") (pintype "passive"))
    )
    (net (code "173") (name "DIO95") (class "Default")
      (node (ref "J24") (pin "A17") (pinfunction "A17_A17") (pintype "passive"))
      (node (ref "J26") (pin "13") (pinfunction "13_13") (pintype "passive"))
    )
    (net (code "174") (name "DONE#_DIO2[1]") (class "Default")
      (node (ref "J1") (pin "15") (pinfunction "15_15") (pintype "bidirectional"))
      (node (ref "J24") (pin "B9") (pinfunction "B9_B9") (pintype "passive"))
    )
    (net (code "175") (name "ESTP+") (class "Default")
      (node (ref "J10") (pin "5") (pinfunction "5_5") (pintype "passive"))
      (node (ref "J11") (pin "5") (pinfunction "5_5") (pintype "passive"))
      (node (ref "J12") (pin "5") (pinfunction "5_5") (pintype "passive"))
      (node (ref "J13") (pin "5") (pinfunction "5_5") (pintype "passive"))
      (node (ref "J25") (pin "2") (pinfunction "2_2") (pintype "passive"))
      (node (ref "J4") (pin "5") (pinfunction "5_5") (pintype "passive"))
      (node (ref "J5") (pin "5") (pinfunction "5_5") (pintype "passive"))
      (node (ref "J6") (pin "5") (pinfunction "5_5") (pintype "passive"))
      (node (ref "J7") (pin "5") (pinfunction "5_5") (pintype "passive"))
      (node (ref "J8") (pin "5") (pinfunction "5_5") (pintype "passive"))
      (node (ref "J9") (pin "5") (pinfunction "5_5") (pintype "passive"))
    )
    (net (code "176") (name "ESTP-") (class "Default")
      (node (ref "J10") (pin "6") (pinfunction "6_6") (pintype "passive"))
      (node (ref "J11") (pin "6") (pinfunction "6_6") (pintype "passive"))
      (node (ref "J12") (pin "6") (pinfunction "6_6") (pintype "passive"))
      (node (ref "J13") (pin "6") (pinfunction "6_6") (pintype "passive"))
      (node (ref "J25") (pin "1") (pinfunction "1_1") (pintype "passive"))
      (node (ref "J4") (pin "6") (pinfunction "6_6") (pintype "passive"))
      (node (ref "J5") (pin "6") (pinfunction "6_6") (pintype "passive"))
      (node (ref "J6") (pin "6") (pinfunction "6_6") (pintype "passive"))
      (node (ref "J7") (pin "6") (pinfunction "6_6") (pintype "passive"))
      (node (ref "J8") (pin "6") (pinfunction "6_6") (pintype "passive"))
      (node (ref "J9") (pin "6") (pinfunction "6_6") (pintype "passive"))
    )
    (net (code "177") (name "GND") (class "Default")
      (node (ref "C1") (pin "2") (pinfunction "2_2") (pintype "passive"))
      (node (ref "C10") (pin "2") (pinfunction "2_2") (pintype "passive"))
      (node (ref "C11") (pin "2") (pinfunction "2_2") (pintype "passive"))
      (node (ref "C12") (pin "2") (pinfunction "-_2") (pintype "bidirectional"))
      (node (ref "C13") (pin "2") (pinfunction "2_2") (pintype "passive"))
      (node (ref "C14") (pin "2") (pinfunction "2_2") (pintype "passive"))
      (node (ref "C15") (pin "2") (pinfunction "2_2") (pintype "passive"))
      (node (ref "C16") (pin "2") (pinfunction "2_2") (pintype "passive"))
      (node (ref "C17") (pin "2") (pinfunction "2_2") (pintype "passive"))
      (node (ref "C18") (pin "2") (pinfunction "2_2") (pintype "passive"))
      (node (ref "C2") (pin "2") (pinfunction "2_2") (pintype "passive"))
      (node (ref "C3") (pin "2") (pinfunction "2_2") (pintype "passive"))
      (node (ref "C4") (pin "2") (pinfunction "2_2") (pintype "passive"))
      (node (ref "C5") (pin "2") (pinfunction "2_2") (pintype "passive"))
      (node (ref "C6") (pin "2") (pinfunction "2_2") (pintype "passive"))
      (node (ref "C7") (pin "2") (pinfunction "2_2") (pintype "passive"))
      (node (ref "C8") (pin "2") (pinfunction "2_2") (pintype "passive"))
      (node (ref "C9") (pin "2") (pinfunction "2_2") (pintype "passive"))
      (node (ref "J1") (pin "14") (pinfunction "14_14") (pintype "bidirectional"))
      (node (ref "J1") (pin "MH1") (pinfunction "MH1_MH1") (pintype "bidirectional"))
      (node (ref "J1") (pin "MH2") (pinfunction "MH2_MH2") (pintype "bidirectional"))
      (node (ref "J10") (pin "10") (pinfunction "10_10") (pintype "passive"))
      (node (ref "J10") (pin "9") (pinfunction "9_9") (pintype "passive"))
      (node (ref "J11") (pin "10") (pinfunction "10_10") (pintype "passive"))
      (node (ref "J11") (pin "9") (pinfunction "9_9") (pintype "passive"))
      (node (ref "J12") (pin "10") (pinfunction "10_10") (pintype "passive"))
      (node (ref "J12") (pin "9") (pinfunction "9_9") (pintype "passive"))
      (node (ref "J13") (pin "10") (pinfunction "10_10") (pintype "passive"))
      (node (ref "J13") (pin "9") (pinfunction "9_9") (pintype "passive"))
      (node (ref "J14") (pin "1") (pinfunction "1_1") (pintype "passive"))
      (node (ref "J14") (pin "11") (pinfunction "11_11") (pintype "passive"))
      (node (ref "J14") (pin "12") (pinfunction "12_12") (pintype "passive"))
      (node (ref "J15") (pin "1") (pinfunction "1_1") (pintype "passive"))
      (node (ref "J15") (pin "11") (pinfunction "11_11") (pintype "passive"))
      (node (ref "J15") (pin "12") (pinfunction "12_12") (pintype "passive"))
      (node (ref "J16") (pin "1") (pinfunction "1_1") (pintype "passive"))
      (node (ref "J16") (pin "11") (pinfunction "11_11") (pintype "passive"))
      (node (ref "J16") (pin "12") (pinfunction "12_12") (pintype "passive"))
      (node (ref "J17") (pin "1") (pinfunction "1_1") (pintype "passive"))
      (node (ref "J17") (pin "11") (pinfunction "11_11") (pintype "passive"))
      (node (ref "J17") (pin "12") (pinfunction "12_12") (pintype "passive"))
      (node (ref "J18") (pin "1") (pinfunction "1_1") (pintype "passive"))
      (node (ref "J18") (pin "11") (pinfunction "11_11") (pintype "passive"))
      (node (ref "J18") (pin "12") (pinfunction "12_12") (pintype "passive"))
      (node (ref "J19") (pin "1") (pinfunction "1_1") (pintype "passive"))
      (node (ref "J19") (pin "11") (pinfunction "11_11") (pintype "passive"))
      (node (ref "J19") (pin "12") (pinfunction "12_12") (pintype "passive"))
      (node (ref "J2") (pin "2") (pinfunction "2_2") (pintype "passive"))
      (node (ref "J2") (pin "3") (pinfunction "3_3") (pintype "passive"))
      (node (ref "J2") (pin "4") (pinfunction "4_4") (pintype "passive"))
      (node (ref "J20") (pin "1") (pinfunction "1_1") (pintype "passive"))
      (node (ref "J20") (pin "11") (pinfunction "11_11") (pintype "passive"))
      (node (ref "J20") (pin "12") (pinfunction "12_12") (pintype "passive"))
      (node (ref "J21") (pin "1") (pinfunction "1_1") (pintype "passive"))
      (node (ref "J21") (pin "11") (pinfunction "11_11") (pintype "passive"))
      (node (ref "J21") (pin "12") (pinfunction "12_12") (pintype "passive"))
      (node (ref "J22") (pin "1") (pinfunction "1_1") (pintype "passive"))
      (node (ref "J22") (pin "11") (pinfunction "11_11") (pintype "passive"))
      (node (ref "J22") (pin "12") (pinfunction "12_12") (pintype "passive"))
      (node (ref "J23") (pin "1") (pinfunction "1_1") (pintype "passive"))
      (node (ref "J23") (pin "11") (pinfunction "11_11") (pintype "passive"))
      (node (ref "J23") (pin "12") (pinfunction "12_12") (pintype "passive"))
      (node (ref "J24") (pin "A12") (pinfunction "A12_A12") (pintype "passive"))
      (node (ref "J24") (pin "A15") (pinfunction "A15_A15") (pintype "passive"))
      (node (ref "J24") (pin "A18") (pinfunction "A18_A18") (pintype "passive"))
      (node (ref "J24") (pin "A21") (pinfunction "A21_A21") (pintype "passive"))
      (node (ref "J24") (pin "A24") (pinfunction "A24_A24") (pintype "passive"))
      (node (ref "J24") (pin "A27") (pinfunction "A27_A27") (pintype "passive"))
      (node (ref "J24") (pin "A3") (pinfunction "A3_A3") (pintype "passive"))
      (node (ref "J24") (pin "A30") (pinfunction "A30_A30") (pintype "passive"))
      (node (ref "J24") (pin "A33") (pinfunction "A33_A33") (pintype "passive"))
      (node (ref "J24") (pin "A36") (pinfunction "A36_A36") (pintype "passive"))
      (node (ref "J24") (pin "A39") (pinfunction "A39_A39") (pintype "passive"))
      (node (ref "J24") (pin "A4") (pinfunction "A4_A4") (pintype "passive"))
      (node (ref "J24") (pin "A9") (pinfunction "A9_A9") (pintype "passive"))
      (node (ref "J24") (pin "B1") (pinfunction "B1_B1") (pintype "passive"))
      (node (ref "J24") (pin "B11") (pinfunction "B11_B11") (pintype "passive"))
      (node (ref "J24") (pin "B14") (pinfunction "B14_B14") (pintype "passive"))
      (node (ref "J24") (pin "B17") (pinfunction "B17_B17") (pintype "passive"))
      (node (ref "J24") (pin "B2") (pinfunction "B2_B2") (pintype "passive"))
      (node (ref "J24") (pin "B20") (pinfunction "B20_B20") (pintype "passive"))
      (node (ref "J24") (pin "B23") (pinfunction "B23_B23") (pintype "passive"))
      (node (ref "J24") (pin "B26") (pinfunction "B26_B26") (pintype "passive"))
      (node (ref "J24") (pin "B29") (pinfunction "B29_B29") (pintype "passive"))
      (node (ref "J24") (pin "B32") (pinfunction "B32_B32") (pintype "passive"))
      (node (ref "J24") (pin "B35") (pinfunction "B35_B35") (pintype "passive"))
      (node (ref "J24") (pin "B38") (pinfunction "B38_B38") (pintype "passive"))
      (node (ref "J24") (pin "B5") (pinfunction "B5_B5") (pintype "passive"))
      (node (ref "J24") (pin "B8") (pinfunction "B8_B8") (pintype "passive"))
      (node (ref "J24") (pin "C10") (pinfunction "C10_C10") (pintype "passive"))
      (node (ref "J24") (pin "C13") (pinfunction "C13_C13") (pintype "passive"))
      (node (ref "J24") (pin "C16") (pinfunction "C16_C16") (pintype "passive"))
      (node (ref "J24") (pin "C19") (pinfunction "C19_C19") (pintype "passive"))
      (node (ref "J24") (pin "C22") (pinfunction "C22_C22") (pintype "passive"))
      (node (ref "J24") (pin "C25") (pinfunction "C25_C25") (pintype "passive"))
      (node (ref "J24") (pin "C28") (pinfunction "C28_C28") (pintype "passive"))
      (node (ref "J24") (pin "C3") (pinfunction "C3_C3") (pintype "passive"))
      (node (ref "J24") (pin "C31") (pinfunction "C31_C31") (pintype "passive"))
      (node (ref "J24") (pin "C34") (pinfunction "C34_C34") (pintype "passive"))
      (node (ref "J24") (pin "C37") (pinfunction "C37_C37") (pintype "passive"))
      (node (ref "J24") (pin "C4") (pinfunction "C4_C4") (pintype "passive"))
      (node (ref "J24") (pin "C40") (pinfunction "C40_C40") (pintype "passive"))
      (node (ref "J24") (pin "C7") (pinfunction "C7_C7") (pintype "passive"))
      (node (ref "J24") (pin "D1") (pinfunction "D1_D1") (pintype "passive"))
      (node (ref "J24") (pin "D12") (pinfunction "D12_D12") (pintype "passive"))
      (node (ref "J24") (pin "D15") (pinfunction "D15_D15") (pintype "passive"))
      (node (ref "J24") (pin "D18") (pinfunction "D18_D18") (pintype "passive"))
      (node (ref "J24") (pin "D2") (pinfunction "D2_D2") (pintype "passive"))
      (node (ref "J24") (pin "D21") (pinfunction "D21_D21") (pintype "passive"))
      (node (ref "J24") (pin "D24") (pinfunction "D24_D24") (pintype "passive"))
      (node (ref "J24") (pin "D27") (pinfunction "D27_D27") (pintype "passive"))
      (node (ref "J24") (pin "D30") (pinfunction "D30_D30") (pintype "passive"))
      (node (ref "J24") (pin "D33") (pinfunction "D33_D33") (pintype "passive"))
      (node (ref "J24") (pin "D36") (pinfunction "D36_D36") (pintype "passive"))
      (node (ref "J24") (pin "D39") (pinfunction "D39_D39") (pintype "passive"))
      (node (ref "J24") (pin "D5") (pinfunction "D5_D5") (pintype "passive"))
      (node (ref "J24") (pin "D9") (pinfunction "D9_D9") (pintype "passive"))
      (node (ref "J24") (pin "E11") (pinfunction "E11_E11") (pintype "passive"))
      (node (ref "J24") (pin "E14") (pinfunction "E14_E14") (pintype "passive"))
      (node (ref "J24") (pin "E17") (pinfunction "E17_E17") (pintype "passive"))
      (node (ref "J24") (pin "E20") (pinfunction "E20_E20") (pintype "passive"))
      (node (ref "J24") (pin "E23") (pinfunction "E23_E23") (pintype "passive"))
      (node (ref "J24") (pin "E26") (pinfunction "E26_E26") (pintype "passive"))
      (node (ref "J24") (pin "E29") (pinfunction "E29_E29") (pintype "passive"))
      (node (ref "J24") (pin "E3") (pinfunction "E3_E3") (pintype "passive"))
      (node (ref "J24") (pin "E32") (pinfunction "E32_E32") (pintype "passive"))
      (node (ref "J24") (pin "E35") (pinfunction "E35_E35") (pintype "passive"))
      (node (ref "J24") (pin "E38") (pinfunction "E38_E38") (pintype "passive"))
      (node (ref "J24") (pin "E4") (pinfunction "E4_E4") (pintype "passive"))
      (node (ref "J24") (pin "E7") (pinfunction "E7_E7") (pintype "passive"))
      (node (ref "J24") (pin "E8") (pinfunction "E8_E8") (pintype "passive"))
      (node (ref "J24") (pin "F1") (pinfunction "F1_F1") (pintype "passive"))
      (node (ref "J24") (pin "F13") (pinfunction "F13_F13") (pintype "passive"))
      (node (ref "J24") (pin "F16") (pinfunction "F16_F16") (pintype "passive"))
      (node (ref "J24") (pin "F19") (pinfunction "F19_F19") (pintype "passive"))
      (node (ref "J24") (pin "F2") (pinfunction "F2_F2") (pintype "passive"))
      (node (ref "J24") (pin "F22") (pinfunction "F22_F22") (pintype "passive"))
      (node (ref "J24") (pin "F25") (pinfunction "F25_F25") (pintype "passive"))
      (node (ref "J24") (pin "F28") (pinfunction "F28_F28") (pintype "passive"))
      (node (ref "J24") (pin "F31") (pinfunction "F31_F31") (pintype "passive"))
      (node (ref "J24") (pin "F34") (pinfunction "F34_F34") (pintype "passive"))
      (node (ref "J24") (pin "F37") (pinfunction "F37_F37") (pintype "passive"))
      (node (ref "J24") (pin "F5") (pinfunction "F5_F5") (pintype "passive"))
      (node (ref "J24") (pin "F6") (pinfunction "F6_F6") (pintype "passive"))
      (node (ref "J25") (pin "3") (pinfunction "3_3") (pintype "passive"))
      (node (ref "J25") (pin "4") (pinfunction "4_4") (pintype "passive"))
      (node (ref "J26") (pin "10") (pinfunction "10_10") (pintype "passive"))
      (node (ref "J26") (pin "12") (pinfunction "12_12") (pintype "passive"))
      (node (ref "J26") (pin "14") (pinfunction "14_14") (pintype "passive"))
      (node (ref "J26") (pin "16") (pinfunction "16_16") (pintype "passive"))
      (node (ref "J26") (pin "18") (pinfunction "18_18") (pintype "passive"))
      (node (ref "J26") (pin "2") (pinfunction "2_2") (pintype "passive"))
      (node (ref "J26") (pin "20") (pinfunction "20_20") (pintype "passive"))
      (node (ref "J26") (pin "4") (pinfunction "4_4") (pintype "passive"))
      (node (ref "J26") (pin "6") (pinfunction "6_6") (pintype "passive"))
      (node (ref "J26") (pin "8") (pinfunction "8_8") (pintype "passive"))
      (node (ref "J27") (pin "10") (pinfunction "10_10") (pintype "passive"))
      (node (ref "J27") (pin "12") (pinfunction "12_12") (pintype "passive"))
      (node (ref "J27") (pin "14") (pinfunction "14_14") (pintype "passive"))
      (node (ref "J27") (pin "16") (pinfunction "16_16") (pintype "passive"))
      (node (ref "J27") (pin "18") (pinfunction "18_18") (pintype "passive"))
      (node (ref "J27") (pin "2") (pinfunction "2_2") (pintype "passive"))
      (node (ref "J27") (pin "20") (pinfunction "20_20") (pintype "passive"))
      (node (ref "J27") (pin "4") (pinfunction "4_4") (pintype "passive"))
      (node (ref "J27") (pin "6") (pinfunction "6_6") (pintype "passive"))
      (node (ref "J27") (pin "8") (pinfunction "8_8") (pintype "passive"))
      (node (ref "J28") (pin "10") (pinfunction "10_10") (pintype "passive"))
      (node (ref "J28") (pin "12") (pinfunction "12_12") (pintype "passive"))
      (node (ref "J28") (pin "14") (pinfunction "14_14") (pintype "passive"))
      (node (ref "J28") (pin "16") (pinfunction "16_16") (pintype "passive"))
      (node (ref "J28") (pin "18") (pinfunction "18_18") (pintype "passive"))
      (node (ref "J28") (pin "2") (pinfunction "2_2") (pintype "passive"))
      (node (ref "J28") (pin "20") (pinfunction "20_20") (pintype "passive"))
      (node (ref "J28") (pin "4") (pinfunction "4_4") (pintype "passive"))
      (node (ref "J28") (pin "6") (pinfunction "6_6") (pintype "passive"))
      (node (ref "J28") (pin "8") (pinfunction "8_8") (pintype "passive"))
      (node (ref "J29") (pin "10") (pinfunction "10_10") (pintype "passive"))
      (node (ref "J29") (pin "12") (pinfunction "12_12") (pintype "passive"))
      (node (ref "J29") (pin "14") (pinfunction "14_14") (pintype "passive"))
      (node (ref "J29") (pin "16") (pinfunction "16_16") (pintype "passive"))
      (node (ref "J29") (pin "18") (pinfunction "18_18") (pintype "passive"))
      (node (ref "J29") (pin "2") (pinfunction "2_2") (pintype "passive"))
      (node (ref "J29") (pin "20") (pinfunction "20_20") (pintype "passive"))
      (node (ref "J29") (pin "4") (pinfunction "4_4") (pintype "passive"))
      (node (ref "J29") (pin "6") (pinfunction "6_6") (pintype "passive"))
      (node (ref "J29") (pin "8") (pinfunction "8_8") (pintype "passive"))
      (node (ref "J3") (pin "21") (pinfunction "21_21") (pintype "passive"))
      (node (ref "J3") (pin "22") (pinfunction "22_22") (pintype "passive"))
      (node (ref "J4") (pin "10") (pinfunction "10_10") (pintype "passive"))
      (node (ref "J4") (pin "9") (pinfunction "9_9") (pintype "passive"))
      (node (ref "J5") (pin "10") (pinfunction "10_10") (pintype "passive"))
      (node (ref "J5") (pin "9") (pinfunction "9_9") (pintype "passive"))
      (node (ref "J6") (pin "10") (pinfunction "10_10") (pintype "passive"))
      (node (ref "J6") (pin "9") (pinfunction "9_9") (pintype "passive"))
      (node (ref "J7") (pin "10") (pinfunction "10_10") (pintype "passive"))
      (node (ref "J7") (pin "9") (pinfunction "9_9") (pintype "passive"))
      (node (ref "J8") (pin "10") (pinfunction "10_10") (pintype "passive"))
      (node (ref "J8") (pin "9") (pinfunction "9_9") (pintype "passive"))
      (node (ref "J9") (pin "10") (pinfunction "10_10") (pintype "passive"))
      (node (ref "J9") (pin "9") (pinfunction "9_9") (pintype "passive"))
      (node (ref "U1") (pin "8") (pinfunction "GND_8") (pintype "power_in"))
      (node (ref "U10") (pin "8") (pinfunction "GND_8") (pintype "power_in"))
      (node (ref "U11") (pin "5") (pinfunction "GND_5") (pintype "passive"))
      (node (ref "U2") (pin "8") (pinfunction "GND_8") (pintype "power_in"))
      (node (ref "U3") (pin "8") (pinfunction "GND_8") (pintype "power_in"))
      (node (ref "U4") (pin "8") (pinfunction "GND_8") (pintype "power_in"))
      (node (ref "U5") (pin "8") (pinfunction "GND_8") (pintype "power_in"))
      (node (ref "U6") (pin "8") (pinfunction "GND_8") (pintype "power_in"))
      (node (ref "U7") (pin "8") (pinfunction "GND_8") (pintype "power_in"))
      (node (ref "U8") (pin "8") (pinfunction "GND_8") (pintype "power_in"))
      (node (ref "U9") (pin "8") (pinfunction "GND_8") (pintype "power_in"))
    )
    (net (code "178") (name "ID_SELECT#[1]") (class "Default")
      (node (ref "J1") (pin "1") (pinfunction "1_1") (pintype "bidirectional"))
      (node (ref "J24") (pin "D7") (pinfunction "D7_D7") (pintype "passive"))
    )
    (net (code "179") (name "MA_M1") (class "Default")
      (node (ref "RN10") (pin "2") (pinfunction "2_2") (pintype "passive"))
      (node (ref "U10") (pin "5") (pinfunction "2Y_5") (pintype "output"))
    )
    (net (code "180") (name "MA_M1_N") (class "Default")
      (node (ref "J13") (pin "2") (pinfunction "2_2") (pintype "passive"))
      (node (ref "J23") (pin "5") (pinfunction "5_5") (pintype "passive"))
      (node (ref "U10") (pin "7") (pinfunction "2B_7") (pintype "input"))
    )
    (net (code "181") (name "MA_M1_P") (class "Default")
      (node (ref "J13") (pin "1") (pinfunction "1_1") (pintype "passive"))
      (node (ref "J23") (pin "6") (pinfunction "6_6") (pintype "passive"))
      (node (ref "U10") (pin "6") (pinfunction "2A_6") (pintype "input"))
    )
    (net (code "182") (name "MA_M2") (class "Default")
      (node (ref "RN5") (pin "2") (pinfunction "2_2") (pintype "passive"))
      (node (ref "U5") (pin "5") (pinfunction "2Y_5") (pintype "output"))
    )
    (net (code "183") (name "MA_M2_N") (class "Default")
      (node (ref "J18") (pin "5") (pinfunction "5_5") (pintype "passive"))
      (node (ref "J8") (pin "2") (pinfunction "2_2") (pintype "passive"))
      (node (ref "U5") (pin "7") (pinfunction "2B_7") (pintype "input"))
    )
    (net (code "184") (name "MA_M2_P") (class "Default")
      (node (ref "J18") (pin "6") (pinfunction "6_6") (pintype "passive"))
      (node (ref "J8") (pin "1") (pinfunction "1_1") (pintype "passive"))
      (node (ref "U5") (pin "6") (pinfunction "2A_6") (pintype "input"))
    )
    (net (code "185") (name "MA_M3") (class "Default")
      (node (ref "RN9") (pin "2") (pinfunction "2_2") (pintype "passive"))
      (node (ref "U9") (pin "5") (pinfunction "2Y_5") (pintype "output"))
    )
    (net (code "186") (name "MA_M3_N") (class "Default")
      (node (ref "J12") (pin "2") (pinfunction "2_2") (pintype "passive"))
      (node (ref "J22") (pin "5") (pinfunction "5_5") (pintype "passive"))
      (node (ref "U9") (pin "7") (pinfunction "2B_7") (pintype "input"))
    )
    (net (code "187") (name "MA_M3_P") (class "Default")
      (node (ref "J12") (pin "1") (pinfunction "1_1") (pintype "passive"))
      (node (ref "J22") (pin "6") (pinfunction "6_6") (pintype "passive"))
      (node (ref "U9") (pin "6") (pinfunction "2A_6") (pintype "input"))
    )
    (net (code "188") (name "MA_M4") (class "Default")
      (node (ref "RN4") (pin "2") (pinfunction "2_2") (pintype "passive"))
      (node (ref "U4") (pin "5") (pinfunction "2Y_5") (pintype "output"))
    )
    (net (code "189") (name "MA_M4_N") (class "Default")
      (node (ref "J17") (pin "5") (pinfunction "5_5") (pintype "passive"))
      (node (ref "J7") (pin "2") (pinfunction "2_2") (pintype "passive"))
      (node (ref "U4") (pin "7") (pinfunction "2B_7") (pintype "input"))
    )
    (net (code "190") (name "MA_M4_P") (class "Default")
      (node (ref "J17") (pin "6") (pinfunction "6_6") (pintype "passive"))
      (node (ref "J7") (pin "1") (pinfunction "1_1") (pintype "passive"))
      (node (ref "U4") (pin "6") (pinfunction "2A_6") (pintype "input"))
    )
    (net (code "191") (name "MA_M5") (class "Default")
      (node (ref "RN8") (pin "2") (pinfunction "2_2") (pintype "passive"))
      (node (ref "U8") (pin "5") (pinfunction "2Y_5") (pintype "output"))
    )
    (net (code "192") (name "MA_M5_N") (class "Default")
      (node (ref "J11") (pin "2") (pinfunction "2_2") (pintype "passive"))
      (node (ref "J21") (pin "5") (pinfunction "5_5") (pintype "passive"))
      (node (ref "U8") (pin "7") (pinfunction "2B_7") (pintype "input"))
    )
    (net (code "193") (name "MA_M5_P") (class "Default")
      (node (ref "J11") (pin "1") (pinfunction "1_1") (pintype "passive"))
      (node (ref "J21") (pin "6") (pinfunction "6_6") (pintype "passive"))
      (node (ref "U8") (pin "6") (pinfunction "2A_6") (pintype "input"))
    )
    (net (code "194") (name "MA_M6") (class "Default")
      (node (ref "RN3") (pin "2") (pinfunction "2_2") (pintype "passive"))
      (node (ref "U3") (pin "5") (pinfunction "2Y_5") (pintype "output"))
    )
    (net (code "195") (name "MA_M6_N") (class "Default")
      (node (ref "J16") (pin "5") (pinfunction "5_5") (pintype "passive"))
      (node (ref "J6") (pin "2") (pinfunction "2_2") (pintype "passive"))
      (node (ref "U3") (pin "7") (pinfunction "2B_7") (pintype "input"))
    )
    (net (code "196") (name "MA_M6_P") (class "Default")
      (node (ref "J16") (pin "6") (pinfunction "6_6") (pintype "passive"))
      (node (ref "J6") (pin "1") (pinfunction "1_1") (pintype "passive"))
      (node (ref "U3") (pin "6") (pinfunction "2A_6") (pintype "input"))
    )
    (net (code "197") (name "MA_M7") (class "Default")
      (node (ref "RN7") (pin "2") (pinfunction "2_2") (pintype "passive"))
      (node (ref "U7") (pin "5") (pinfunction "2Y_5") (pintype "output"))
    )
    (net (code "198") (name "MA_M7_N") (class "Default")
      (node (ref "J10") (pin "2") (pinfunction "2_2") (pintype "passive"))
      (node (ref "J20") (pin "5") (pinfunction "5_5") (pintype "passive"))
      (node (ref "U7") (pin "7") (pinfunction "2B_7") (pintype "input"))
    )
    (net (code "199") (name "MA_M7_P") (class "Default")
      (node (ref "J10") (pin "1") (pinfunction "1_1") (pintype "passive"))
      (node (ref "J20") (pin "6") (pinfunction "6_6") (pintype "passive"))
      (node (ref "U7") (pin "6") (pinfunction "2A_6") (pintype "input"))
    )
    (net (code "200") (name "MA_M8") (class "Default")
      (node (ref "RN2") (pin "2") (pinfunction "2_2") (pintype "passive"))
      (node (ref "U2") (pin "5") (pinfunction "2Y_5") (pintype "output"))
    )
    (net (code "201") (name "MA_M8_N") (class "Default")
      (node (ref "J15") (pin "5") (pinfunction "5_5") (pintype "passive"))
      (node (ref "J5") (pin "2") (pinfunction "2_2") (pintype "passive"))
      (node (ref "U2") (pin "7") (pinfunction "2B_7") (pintype "input"))
    )
    (net (code "202") (name "MA_M8_P") (class "Default")
      (node (ref "J15") (pin "6") (pinfunction "6_6") (pintype "passive"))
      (node (ref "J5") (pin "1") (pinfunction "1_1") (pintype "passive"))
      (node (ref "U2") (pin "6") (pinfunction "2A_6") (pintype "input"))
    )
    (net (code "203") (name "MA_M9") (class "Default")
      (node (ref "RN6") (pin "2") (pinfunction "2_2") (pintype "passive"))
      (node (ref "U6") (pin "5") (pinfunction "2Y_5") (pintype "output"))
    )
    (net (code "204") (name "MA_M9_N") (class "Default")
      (node (ref "J19") (pin "5") (pinfunction "5_5") (pintype "passive"))
      (node (ref "J9") (pin "2") (pinfunction "2_2") (pintype "passive"))
      (node (ref "U6") (pin "7") (pinfunction "2B_7") (pintype "input"))
    )
    (net (code "205") (name "MA_M9_P") (class "Default")
      (node (ref "J19") (pin "6") (pinfunction "6_6") (pintype "passive"))
      (node (ref "J9") (pin "1") (pinfunction "1_1") (pintype "passive"))
      (node (ref "U6") (pin "6") (pinfunction "2A_6") (pintype "input"))
    )
    (net (code "206") (name "MA_M10") (class "Default")
      (node (ref "RN1") (pin "2") (pinfunction "2_2") (pintype "passive"))
      (node (ref "U1") (pin "5") (pinfunction "2Y_5") (pintype "output"))
    )
    (net (code "207") (name "MA_M10_N") (class "Default")
      (node (ref "J14") (pin "5") (pinfunction "5_5") (pintype "passive"))
      (node (ref "J4") (pin "2") (pinfunction "2_2") (pintype "passive"))
      (node (ref "U1") (pin "7") (pinfunction "2B_7") (pintype "input"))
    )
    (net (code "208") (name "MA_M10_P") (class "Default")
      (node (ref "J14") (pin "6") (pinfunction "6_6") (pintype "passive"))
      (node (ref "J4") (pin "1") (pinfunction "1_1") (pintype "passive"))
      (node (ref "U1") (pin "6") (pinfunction "2A_6") (pintype "input"))
    )
    (net (code "209") (name "MISO_DIO6[1]") (class "Default")
      (node (ref "J1") (pin "12") (pinfunction "12_12") (pintype "bidirectional"))
      (node (ref "J24") (pin "E12") (pinfunction "E12_E12") (pintype "passive"))
    )
    (net (code "210") (name "MOSI_DIO7[1]") (class "Default")
      (node (ref "J1") (pin "6") (pinfunction "6_6") (pintype "bidirectional"))
      (node (ref "J24") (pin "B10") (pinfunction "B10_B10") (pintype "passive"))
    )
    (net (code "211") (name "Net-(U11-~{ERROR})") (class "Default")
      (node (ref "R2") (pin "2") (pinfunction "2_2") (pintype "passive"))
      (node (ref "U11") (pin "4") (pinfunction "~{ERROR}_4") (pintype "input"))
    )
    (net (code "212") (name "Net-(U11-~{SD})") (class "Default")
      (node (ref "R1") (pin "2") (pinfunction "2_2") (pintype "passive"))
      (node (ref "U11") (pin "1") (pinfunction "~{SD}_1") (pintype "input"))
    )
    (net (code "213") (name "OSCLK_DIO0[1]") (class "Default")
      (node (ref "J1") (pin "10") (pinfunction "10_10") (pintype "bidirectional"))
      (node (ref "J24") (pin "D10") (pinfunction "D10_D10") (pintype "passive"))
    )
    (net (code "214") (name "SLEEP[1]") (class "Default")
      (node (ref "J1") (pin "8") (pinfunction "8_8") (pintype "bidirectional"))
      (node (ref "J24") (pin "C8") (pinfunction "C8_C8") (pintype "passive"))
    )
    (net (code "215") (name "SLO_M1") (class "Default")
      (node (ref "RN10") (pin "1") (pinfunction "1_1") (pintype "passive"))
      (node (ref "U10") (pin "3") (pinfunction "1Y_3") (pintype "output"))
    )
    (net (code "216") (name "SLO_M1_N") (class "Default")
      (node (ref "J13") (pin "4") (pinfunction "4_4") (pintype "passive"))
      (node (ref "J23") (pin "3") (pinfunction "3_3") (pintype "passive"))
      (node (ref "U10") (pin "1") (pinfunction "1B_1") (pintype "input"))
    )
    (net (code "217") (name "SLO_M1_P") (class "Default")
      (node (ref "J13") (pin "3") (pinfunction "3_3") (pintype "passive"))
      (node (ref "J23") (pin "4") (pinfunction "4_4") (pintype "passive"))
      (node (ref "U10") (pin "2") (pinfunction "1A_2") (pintype "input"))
    )
    (net (code "218") (name "SLO_M2") (class "Default")
      (node (ref "RN5") (pin "1") (pinfunction "1_1") (pintype "passive"))
      (node (ref "U5") (pin "3") (pinfunction "1Y_3") (pintype "output"))
    )
    (net (code "219") (name "SLO_M2_N") (class "Default")
      (node (ref "J18") (pin "3") (pinfunction "3_3") (pintype "passive"))
      (node (ref "J8") (pin "4") (pinfunction "4_4") (pintype "passive"))
      (node (ref "U5") (pin "1") (pinfunction "1B_1") (pintype "input"))
    )
    (net (code "220") (name "SLO_M2_P") (class "Default")
      (node (ref "J18") (pin "4") (pinfunction "4_4") (pintype "passive"))
      (node (ref "J8") (pin "3") (pinfunction "3_3") (pintype "passive"))
      (node (ref "U5") (pin "2") (pinfunction "1A_2") (pintype "input"))
    )
    (net (code "221") (name "SLO_M3") (class "Default")
      (node (ref "RN9") (pin "1") (pinfunction "1_1") (pintype "passive"))
      (node (ref "U9") (pin "3") (pinfunction "1Y_3") (pintype "output"))
    )
    (net (code "222") (name "SLO_M3_N") (class "Default")
      (node (ref "J12") (pin "4") (pinfunction "4_4") (pintype "passive"))
      (node (ref "J22") (pin "3") (pinfunction "3_3") (pintype "passive"))
      (node (ref "U9") (pin "1") (pinfunction "1B_1") (pintype "input"))
    )
    (net (code "223") (name "SLO_M3_P") (class "Default")
      (node (ref "J12") (pin "3") (pinfunction "3_3") (pintype "passive"))
      (node (ref "J22") (pin "4") (pinfunction "4_4") (pintype "passive"))
      (node (ref "U9") (pin "2") (pinfunction "1A_2") (pintype "input"))
    )
    (net (code "224") (name "SLO_M4") (class "Default")
      (node (ref "RN4") (pin "1") (pinfunction "1_1") (pintype "passive"))
      (node (ref "U4") (pin "3") (pinfunction "1Y_3") (pintype "output"))
    )
    (net (code "225") (name "SLO_M4_N") (class "Default")
      (node (ref "J17") (pin "3") (pinfunction "3_3") (pintype "passive"))
      (node (ref "J7") (pin "4") (pinfunction "4_4") (pintype "passive"))
      (node (ref "U4") (pin "1") (pinfunction "1B_1") (pintype "input"))
    )
    (net (code "226") (name "SLO_M4_P") (class "Default")
      (node (ref "J17") (pin "4") (pinfunction "4_4") (pintype "passive"))
      (node (ref "J7") (pin "3") (pinfunction "3_3") (pintype "passive"))
      (node (ref "U4") (pin "2") (pinfunction "1A_2") (pintype "input"))
    )
    (net (code "227") (name "SLO_M5") (class "Default")
      (node (ref "RN8") (pin "1") (pinfunction "1_1") (pintype "passive"))
      (node (ref "U8") (pin "3") (pinfunction "1Y_3") (pintype "output"))
    )
    (net (code "228") (name "SLO_M5_N") (class "Default")
      (node (ref "J11") (pin "4") (pinfunction "4_4") (pintype "passive"))
      (node (ref "J21") (pin "3") (pinfunction "3_3") (pintype "passive"))
      (node (ref "U8") (pin "1") (pinfunction "1B_1") (pintype "input"))
    )
    (net (code "229") (name "SLO_M5_P") (class "Default")
      (node (ref "J11") (pin "3") (pinfunction "3_3") (pintype "passive"))
      (node (ref "J21") (pin "4") (pinfunction "4_4") (pintype "passive"))
      (node (ref "U8") (pin "2") (pinfunction "1A_2") (pintype "input"))
    )
    (net (code "230") (name "SLO_M6") (class "Default")
      (node (ref "RN3") (pin "1") (pinfunction "1_1") (pintype "passive"))
      (node (ref "U3") (pin "3") (pinfunction "1Y_3") (pintype "output"))
    )
    (net (code "231") (name "SLO_M6_N") (class "Default")
      (node (ref "J16") (pin "3") (pinfunction "3_3") (pintype "passive"))
      (node (ref "J6") (pin "4") (pinfunction "4_4") (pintype "passive"))
      (node (ref "U3") (pin "1") (pinfunction "1B_1") (pintype "input"))
    )
    (net (code "232") (name "SLO_M6_P") (class "Default")
      (node (ref "J16") (pin "4") (pinfunction "4_4") (pintype "passive"))
      (node (ref "J6") (pin "3") (pinfunction "3_3") (pintype "passive"))
      (node (ref "U3") (pin "2") (pinfunction "1A_2") (pintype "input"))
    )
    (net (code "233") (name "SLO_M7") (class "Default")
      (node (ref "RN7") (pin "1") (pinfunction "1_1") (pintype "passive"))
      (node (ref "U7") (pin "3") (pinfunction "1Y_3") (pintype "output"))
    )
    (net (code "234") (name "SLO_M7_N") (class "Default")
      (node (ref "J10") (pin "4") (pinfunction "4_4") (pintype "passive"))
      (node (ref "J20") (pin "3") (pinfunction "3_3") (pintype "passive"))
      (node (ref "U7") (pin "1") (pinfunction "1B_1") (pintype "input"))
    )
    (net (code "235") (name "SLO_M7_P") (class "Default")
      (node (ref "J10") (pin "3") (pinfunction "3_3") (pintype "passive"))
      (node (ref "J20") (pin "4") (pinfunction "4_4") (pintype "passive"))
      (node (ref "U7") (pin "2") (pinfunction "1A_2") (pintype "input"))
    )
    (net (code "236") (name "SLO_M8") (class "Default")
      (node (ref "RN2") (pin "1") (pinfunction "1_1") (pintype "passive"))
      (node (ref "U2") (pin "3") (pinfunction "1Y_3") (pintype "output"))
    )
    (net (code "237") (name "SLO_M8_N") (class "Default")
      (node (ref "J15") (pin "3") (pinfunction "3_3") (pintype "passive"))
      (node (ref "J5") (pin "4") (pinfunction "4_4") (pintype "passive"))
      (node (ref "U2") (pin "1") (pinfunction "1B_1") (pintype "input"))
    )
    (net (code "238") (name "SLO_M8_P") (class "Default")
      (node (ref "J15") (pin "4") (pinfunction "4_4") (pintype "passive"))
      (node (ref "J5") (pin "3") (pinfunction "3_3") (pintype "passive"))
      (node (ref "U2") (pin "2") (pinfunction "1A_2") (pintype "input"))
    )
    (net (code "239") (name "SLO_M9") (class "Default")
      (node (ref "RN6") (pin "1") (pinfunction "1_1") (pintype "passive"))
      (node (ref "U6") (pin "3") (pinfunction "1Y_3") (pintype "output"))
    )
    (net (code "240") (name "SLO_M9_N") (class "Default")
      (node (ref "J19") (pin "3") (pinfunction "3_3") (pintype "passive"))
      (node (ref "J9") (pin "4") (pinfunction "4_4") (pintype "passive"))
      (node (ref "U6") (pin "1") (pinfunction "1B_1") (pintype "input"))
    )
    (net (code "241") (name "SLO_M9_P") (class "Default")
      (node (ref "J19") (pin "4") (pinfunction "4_4") (pintype "passive"))
      (node (ref "J9") (pin "3") (pinfunction "3_3") (pintype "passive"))
      (node (ref "U6") (pin "2") (pinfunction "1A_2") (pintype "input"))
    )
    (net (code "242") (name "SLO_M10") (class "Default")
      (node (ref "RN1") (pin "1") (pinfunction "1_1") (pintype "passive"))
      (node (ref "U1") (pin "3") (pinfunction "1Y_3") (pintype "output"))
    )
    (net (code "243") (name "SLO_M10_N") (class "Default")
      (node (ref "J14") (pin "3") (pinfunction "3_3") (pintype "passive"))
      (node (ref "J4") (pin "4") (pinfunction "4_4") (pintype "passive"))
      (node (ref "U1") (pin "1") (pinfunction "1B_1") (pintype "input"))
    )
    (net (code "244") (name "SLO_M10_P") (class "Default")
      (node (ref "J14") (pin "4") (pinfunction "4_4") (pintype "passive"))
      (node (ref "J4") (pin "3") (pinfunction "3_3") (pintype "passive"))
      (node (ref "U1") (pin "2") (pinfunction "1A_2") (pintype "input"))
    )
    (net (code "245") (name "SPICS#_DIO5[1]") (class "Default")
      (node (ref "J1") (pin "2") (pinfunction "2_2") (pintype "bidirectional"))
      (node (ref "J24") (pin "A10") (pinfunction "A10_A10") (pintype "passive"))
    )
    (net (code "246") (name "SPIFUNC_DIO4[1]") (class "Default")
      (node (ref "J1") (pin "7") (pinfunction "7_7") (pintype "bidirectional"))
      (node (ref "J24") (pin "E9") (pinfunction "E9_E9") (pintype "passive"))
    )
    (net (code "247") (name "SPI_CLK[1]") (class "Default")
      (node (ref "J1") (pin "11") (pinfunction "11_11") (pintype "bidirectional"))
      (node (ref "J24") (pin "A11") (pinfunction "A11_A11") (pintype "passive"))
    )
    (net (code "248") (name "TRIG_DIO1[1]") (class "Default")
      (node (ref "J1") (pin "5") (pinfunction "5_5") (pintype "bidirectional"))
      (node (ref "J24") (pin "D11") (pinfunction "D11_D11") (pintype "passive"))
    )
    (net (code "249") (name "unconnected-(J1-Pad3)") (class "Default")
      (node (ref "J1") (pin "3") (pinfunction "3_3") (pintype "bidirectional"))
    )
    (net (code "250") (name "unconnected-(J1-Pad13)") (class "Default")
      (node (ref "J1") (pin "13") (pinfunction "13_13") (pintype "bidirectional"))
    )
    (net (code "251") (name "unconnected-(J24-PadA1)") (class "Default")
      (node (ref "J24") (pin "A1") (pinfunction "A1_A1") (pintype "passive"))
    )
    (net (code "252") (name "unconnected-(J24-PadA2)") (class "Default")
      (node (ref "J24") (pin "A2") (pinfunction "A2_A2") (pintype "passive"))
    )
    (net (code "253") (name "unconnected-(J24-PadA5)") (class "Default")
      (node (ref "J24") (pin "A5") (pinfunction "A5_A5") (pintype "passive"))
    )
    (net (code "254") (name "unconnected-(J24-PadA6)") (class "Default")
      (node (ref "J24") (pin "A6") (pinfunction "A6_A6") (pintype "passive"))
    )
    (net (code "255") (name "unconnected-(J24-PadA7)") (class "Default")
      (node (ref "J24") (pin "A7") (pinfunction "A7_A7") (pintype "passive"))
    )
    (net (code "256") (name "unconnected-(J24-PadA8)") (class "Default")
      (node (ref "J24") (pin "A8") (pinfunction "A8_A8") (pintype "passive"))
    )
    (net (code "257") (name "unconnected-(J24-PadA13)") (class "Default")
      (node (ref "J24") (pin "A13") (pinfunction "A13_A13") (pintype "passive"))
    )
    (net (code "258") (name "unconnected-(J24-PadA14)") (class "Default")
      (node (ref "J24") (pin "A14") (pinfunction "A14_A14") (pintype "passive"))
    )
    (net (code "259") (name "unconnected-(J24-PadB3)") (class "Default")
      (node (ref "J24") (pin "B3") (pinfunction "B3_B3") (pintype "passive"))
    )
    (net (code "260") (name "unconnected-(J24-PadB4)") (class "Default")
      (node (ref "J24") (pin "B4") (pinfunction "B4_B4") (pintype "passive"))
    )
    (net (code "261") (name "unconnected-(J24-PadB6)") (class "Default")
      (node (ref "J24") (pin "B6") (pinfunction "B6_B6") (pintype "passive"))
    )
    (net (code "262") (name "unconnected-(J24-PadB7)") (class "Default")
      (node (ref "J24") (pin "B7") (pinfunction "B7_B7") (pintype "passive"))
    )
    (net (code "263") (name "unconnected-(J24-PadB12)") (class "Default")
      (node (ref "J24") (pin "B12") (pinfunction "B12_B12") (pintype "passive"))
    )
    (net (code "264") (name "unconnected-(J24-PadB13)") (class "Default")
      (node (ref "J24") (pin "B13") (pinfunction "B13_B13") (pintype "passive"))
    )
    (net (code "265") (name "unconnected-(J24-PadB16)") (class "Default")
      (node (ref "J24") (pin "B16") (pinfunction "B16_B16") (pintype "passive"))
    )
    (net (code "266") (name "unconnected-(J24-PadB40)") (class "Default")
      (node (ref "J24") (pin "B40") (pinfunction "B40_B40") (pintype "passive"))
    )
    (net (code "267") (name "unconnected-(J24-PadC1)") (class "Default")
      (node (ref "J24") (pin "C1") (pinfunction "C1_C1") (pintype "passive"))
    )
    (net (code "268") (name "unconnected-(J24-PadC2)") (class "Default")
      (node (ref "J24") (pin "C2") (pinfunction "C2_C2") (pintype "passive"))
    )
    (net (code "269") (name "unconnected-(J24-PadC5)") (class "Default")
      (node (ref "J24") (pin "C5") (pinfunction "C5_C5") (pintype "passive"))
    )
    (net (code "270") (name "unconnected-(J24-PadC6)") (class "Default")
      (node (ref "J24") (pin "C6") (pinfunction "C6_C6") (pintype "passive"))
    )
    (net (code "271") (name "unconnected-(J24-PadC9)") (class "Default")
      (node (ref "J24") (pin "C9") (pinfunction "C9_C9") (pintype "passive"))
    )
    (net (code "272") (name "unconnected-(J24-PadC11)") (class "Default")
      (node (ref "J24") (pin "C11") (pinfunction "C11_C11") (pintype "passive"))
    )
    (net (code "273") (name "unconnected-(J24-PadC12)") (class "Default")
      (node (ref "J24") (pin "C12") (pinfunction "C12_C12") (pintype "passive"))
    )
    (net (code "274") (name "unconnected-(J24-PadC14)") (class "Default")
      (node (ref "J24") (pin "C14") (pinfunction "C14_C14") (pintype "passive"))
    )
    (net (code "275") (name "unconnected-(J24-PadC15)") (class "Default")
      (node (ref "J24") (pin "C15") (pinfunction "C15_C15") (pintype "passive"))
    )
    (net (code "276") (name "unconnected-(J24-PadD3)") (class "Default")
      (node (ref "J24") (pin "D3") (pinfunction "D3_D3") (pintype "passive"))
    )
    (net (code "277") (name "unconnected-(J24-PadD4)") (class "Default")
      (node (ref "J24") (pin "D4") (pinfunction "D4_D4") (pintype "passive"))
    )
    (net (code "278") (name "unconnected-(J24-PadD6)") (class "Default")
      (node (ref "J24") (pin "D6") (pinfunction "D6_D6") (pintype "passive"))
    )
    (net (code "279") (name "unconnected-(J24-PadD13)") (class "Default")
      (node (ref "J24") (pin "D13") (pinfunction "D13_D13") (pintype "passive"))
    )
    (net (code "280") (name "unconnected-(J24-PadD14)") (class "Default")
      (node (ref "J24") (pin "D14") (pinfunction "D14_D14") (pintype "passive"))
    )
    (net (code "281") (name "unconnected-(J24-PadD40)") (class "Default")
      (node (ref "J24") (pin "D40") (pinfunction "D40_D40") (pintype "passive"))
    )
    (net (code "282") (name "unconnected-(J24-PadE1)") (class "Default")
      (node (ref "J24") (pin "E1") (pinfunction "E1_E1") (pintype "passive"))
    )
    (net (code "283") (name "unconnected-(J24-PadE2)") (class "Default")
      (node (ref "J24") (pin "E2") (pinfunction "E2_E2") (pintype "passive"))
    )
    (net (code "284") (name "unconnected-(J24-PadE5)") (class "Default")
      (node (ref "J24") (pin "E5") (pinfunction "E5_E5") (pintype "passive"))
    )
    (net (code "285") (name "unconnected-(J24-PadE6)") (class "Default")
      (node (ref "J24") (pin "E6") (pinfunction "E6_E6") (pintype "passive"))
    )
    (net (code "286") (name "unconnected-(J24-PadE10)") (class "Default")
      (node (ref "J24") (pin "E10") (pinfunction "E10_E10") (pintype "passive"))
    )
    (net (code "287") (name "unconnected-(J24-PadE13)") (class "Default")
      (node (ref "J24") (pin "E13") (pinfunction "E13_E13") (pintype "passive"))
    )
    (net (code "288") (name "unconnected-(J24-PadE39)") (class "Default")
      (node (ref "J24") (pin "E39") (pinfunction "E39_E39") (pintype "passive"))
    )
    (net (code "289") (name "unconnected-(J24-PadE40)") (class "Default")
      (node (ref "J24") (pin "E40") (pinfunction "E40_E40") (pintype "passive"))
    )
    (net (code "290") (name "unconnected-(J24-PadF3)") (class "Default")
      (node (ref "J24") (pin "F3") (pinfunction "F3_F3") (pintype "passive"))
    )
    (net (code "291") (name "unconnected-(J24-PadF4)") (class "Default")
      (node (ref "J24") (pin "F4") (pinfunction "F4_F4") (pintype "passive"))
    )
    (net (code "292") (name "unconnected-(J24-PadF7)") (class "Default")
      (node (ref "J24") (pin "F7") (pinfunction "F7_F7") (pintype "passive"))
    )
    (net (code "293") (name "unconnected-(J24-PadF14)") (class "Default")
      (node (ref "J24") (pin "F14") (pinfunction "F14_F14") (pintype "passive"))
    )
    (net (code "294") (name "unconnected-(J24-PadF39)") (class "Default")
      (node (ref "J24") (pin "F39") (pinfunction "F39_F39") (pintype "passive"))
    )
    (net (code "295") (name "unconnected-(J24-PadF40)") (class "Default")
      (node (ref "J24") (pin "F40") (pinfunction "F40_F40") (pintype "passive"))
    )
    (net (code "296") (name "unconnected-(U1-~{G}-Pad12)") (class "Default")
      (node (ref "U1") (pin "12") (pinfunction "~{G}_12") (pintype "passive"))
    )
    (net (code "297") (name "unconnected-(U2-~{G}-Pad12)") (class "Default")
      (node (ref "U2") (pin "12") (pinfunction "~{G}_12") (pintype "passive"))
    )
    (net (code "298") (name "unconnected-(U3-~{G}-Pad12)") (class "Default")
      (node (ref "U3") (pin "12") (pinfunction "~{G}_12") (pintype "passive"))
    )
    (net (code "299") (name "unconnected-(U4-~{G}-Pad12)") (class "Default")
      (node (ref "U4") (pin "12") (pinfunction "~{G}_12") (pintype "passive"))
    )
    (net (code "300") (name "unconnected-(U5-~{G}-Pad12)") (class "Default")
      (node (ref "U5") (pin "12") (pinfunction "~{G}_12") (pintype "passive"))
    )
    (net (code "301") (name "unconnected-(U6-~{G}-Pad12)") (class "Default")
      (node (ref "U6") (pin "12") (pinfunction "~{G}_12") (pintype "passive"))
    )
    (net (code "302") (name "unconnected-(U7-~{G}-Pad12)") (class "Default")
      (node (ref "U7") (pin "12") (pinfunction "~{G}_12") (pintype "passive"))
    )
    (net (code "303") (name "unconnected-(U8-~{G}-Pad12)") (class "Default")
      (node (ref "U8") (pin "12") (pinfunction "~{G}_12") (pintype "passive"))
    )
    (net (code "304") (name "unconnected-(U9-~{G}-Pad12)") (class "Default")
      (node (ref "U9") (pin "12") (pinfunction "~{G}_12") (pintype "passive"))
    )
    (net (code "305") (name "unconnected-(U10-~{G}-Pad12)") (class "Default")
      (node (ref "U10") (pin "12") (pinfunction "~{G}_12") (pintype "passive"))
    )
  )
)
